# DLP.net
KiCad netlist of a schematic drawn in Altium Designer
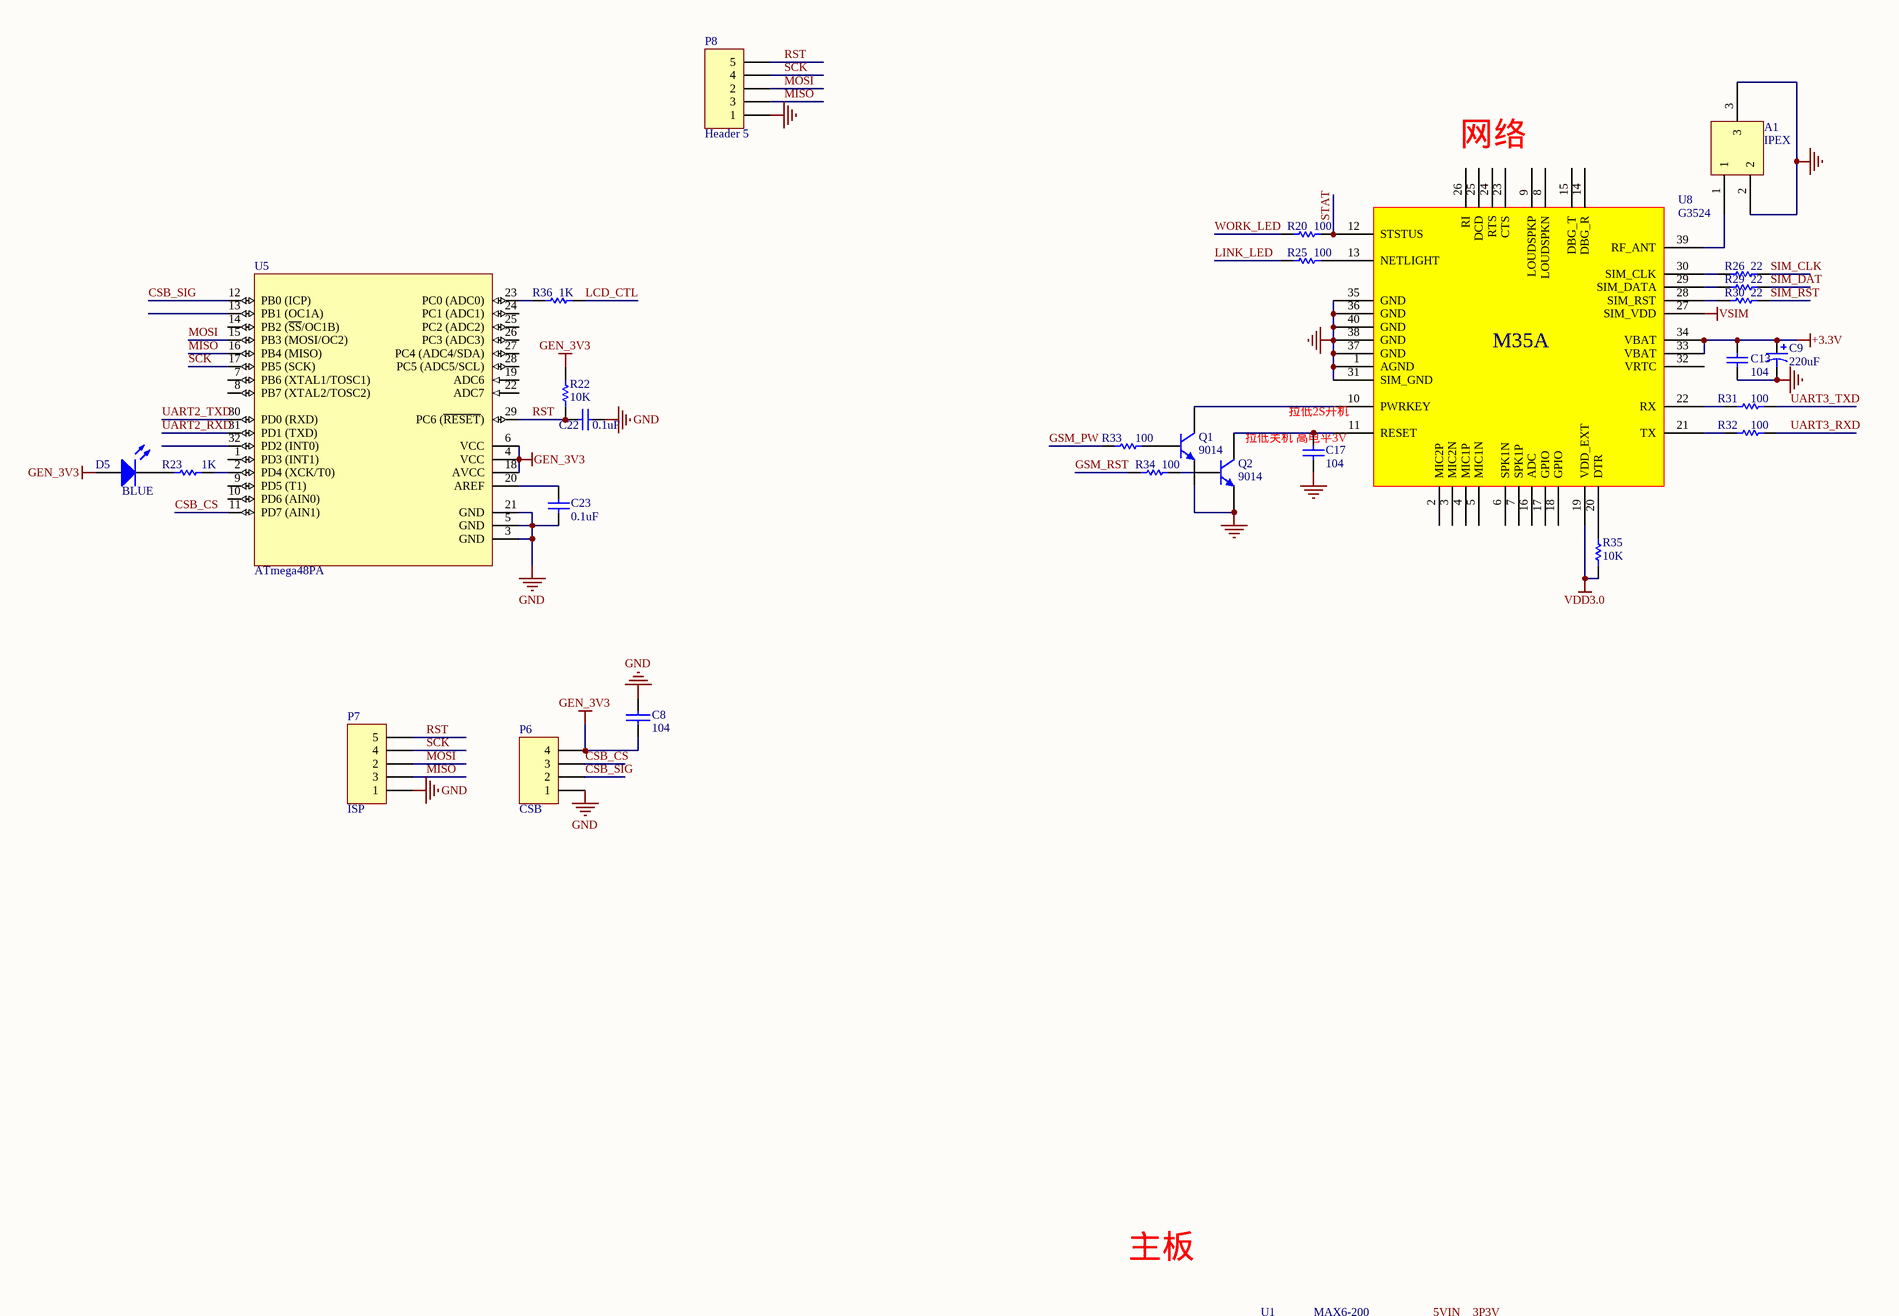
[diagram p0: DLP.SchDoc, top left]
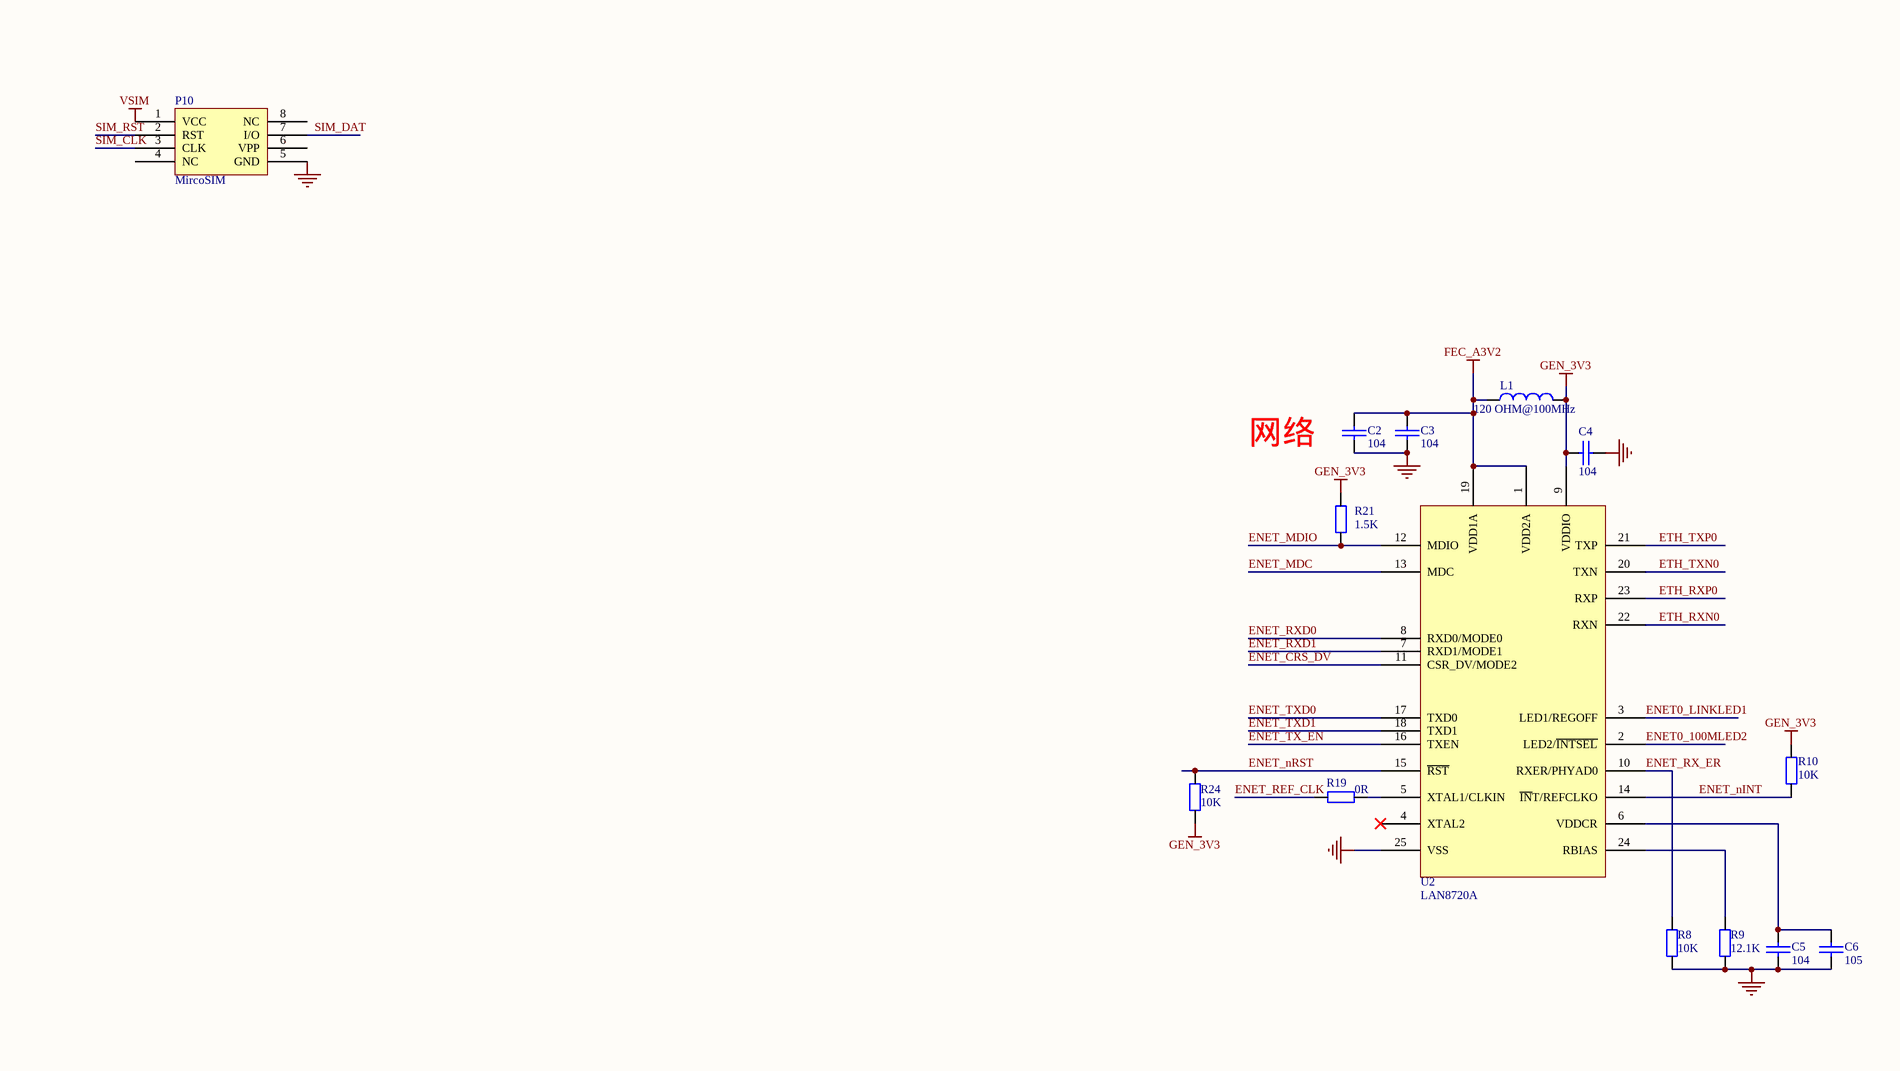
[diagram p1: DLP.SchDoc, top right]
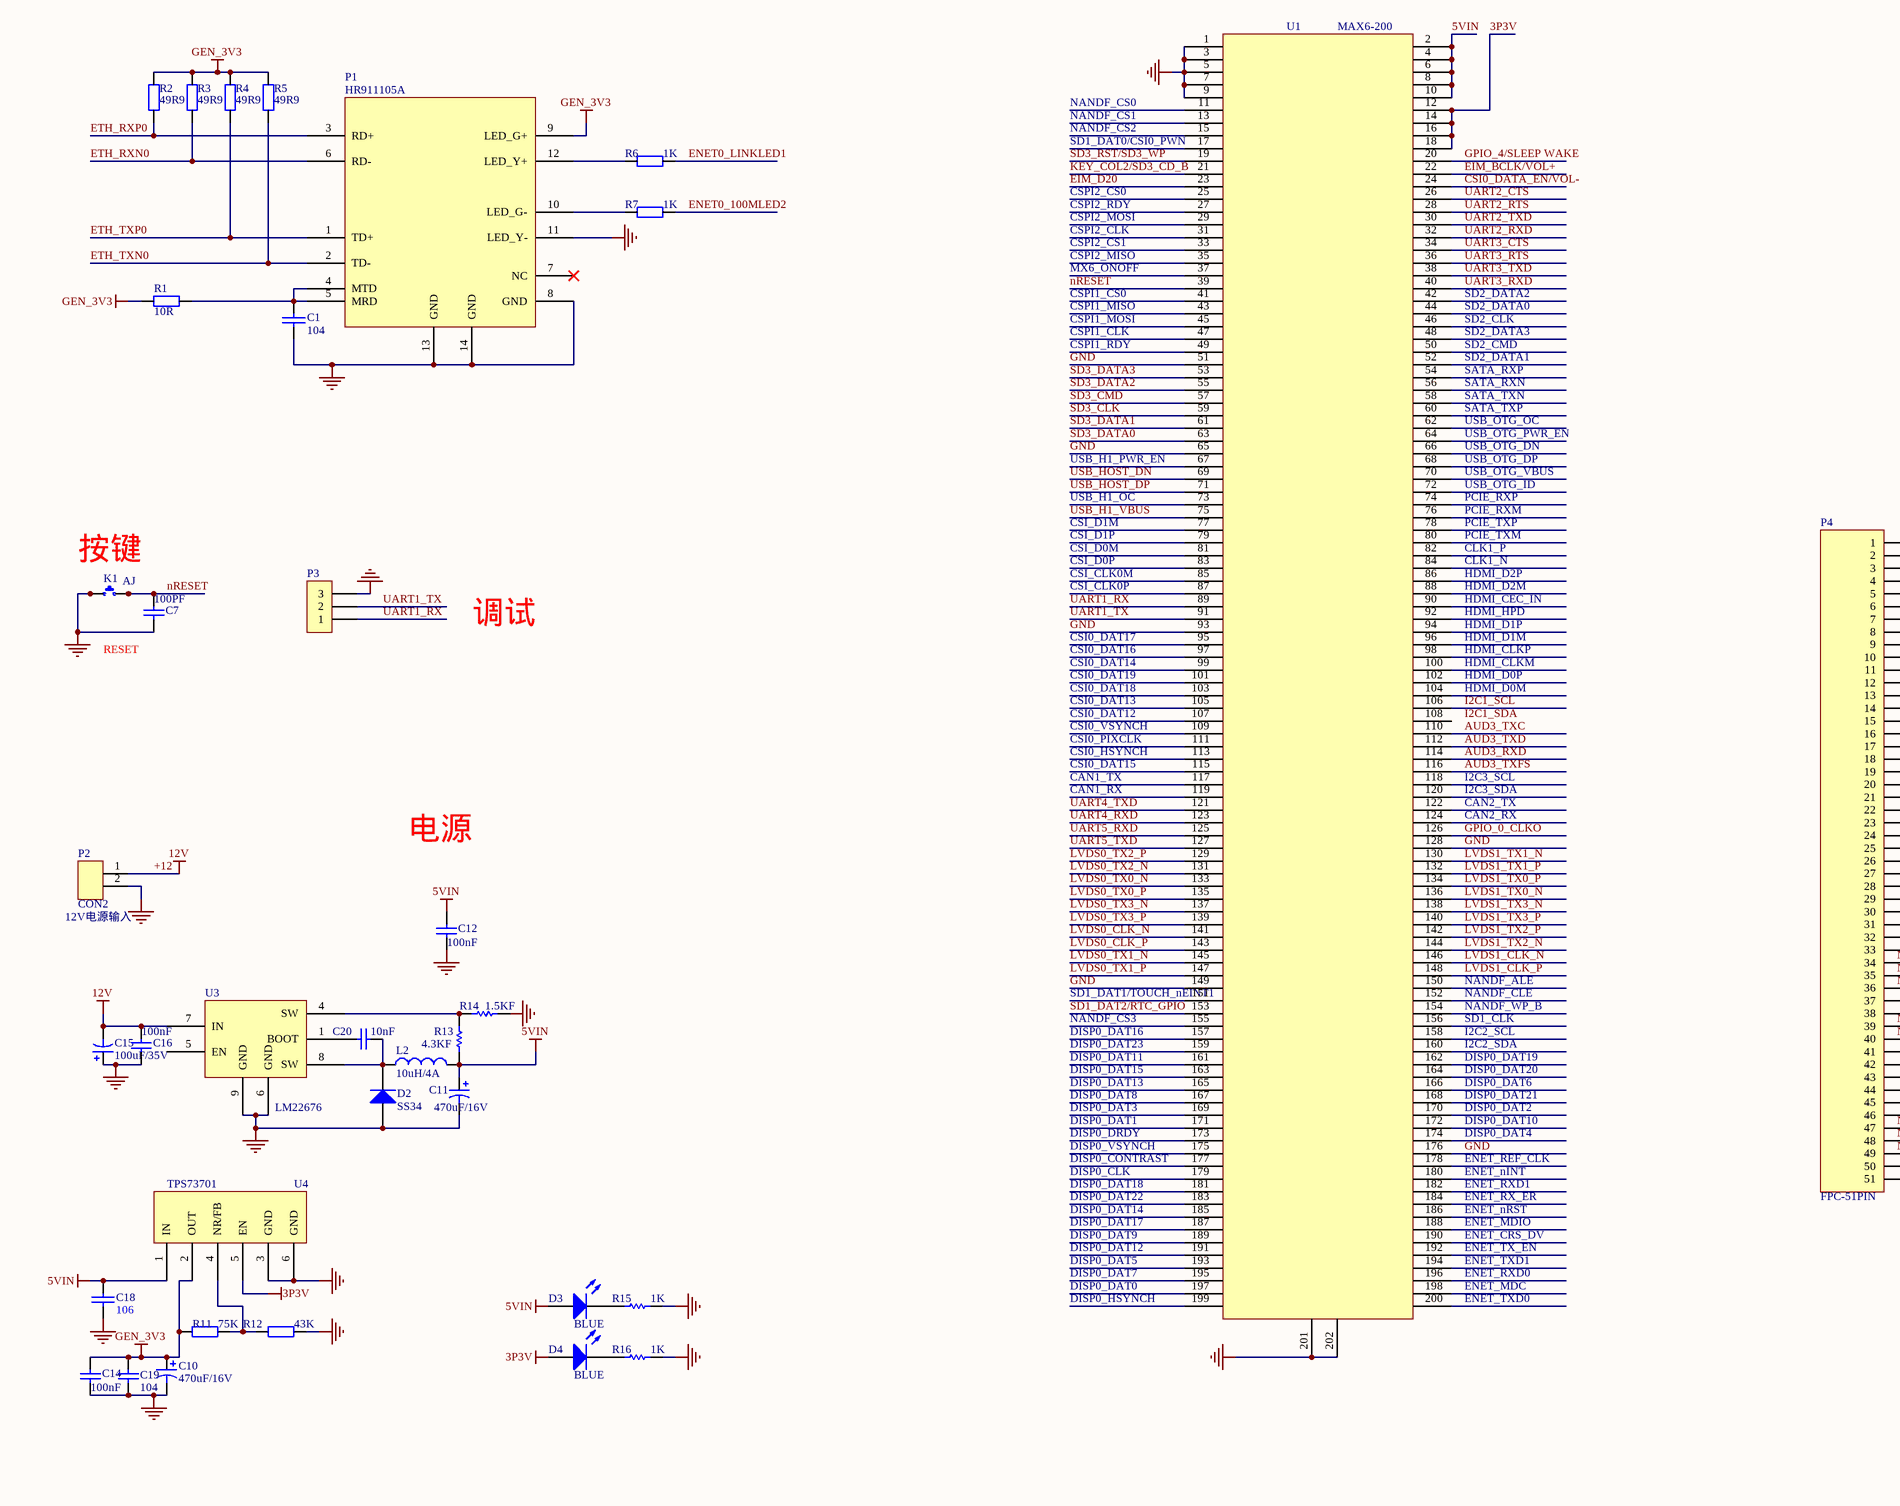
[diagram p2: DLP.SchDoc, bottom left]
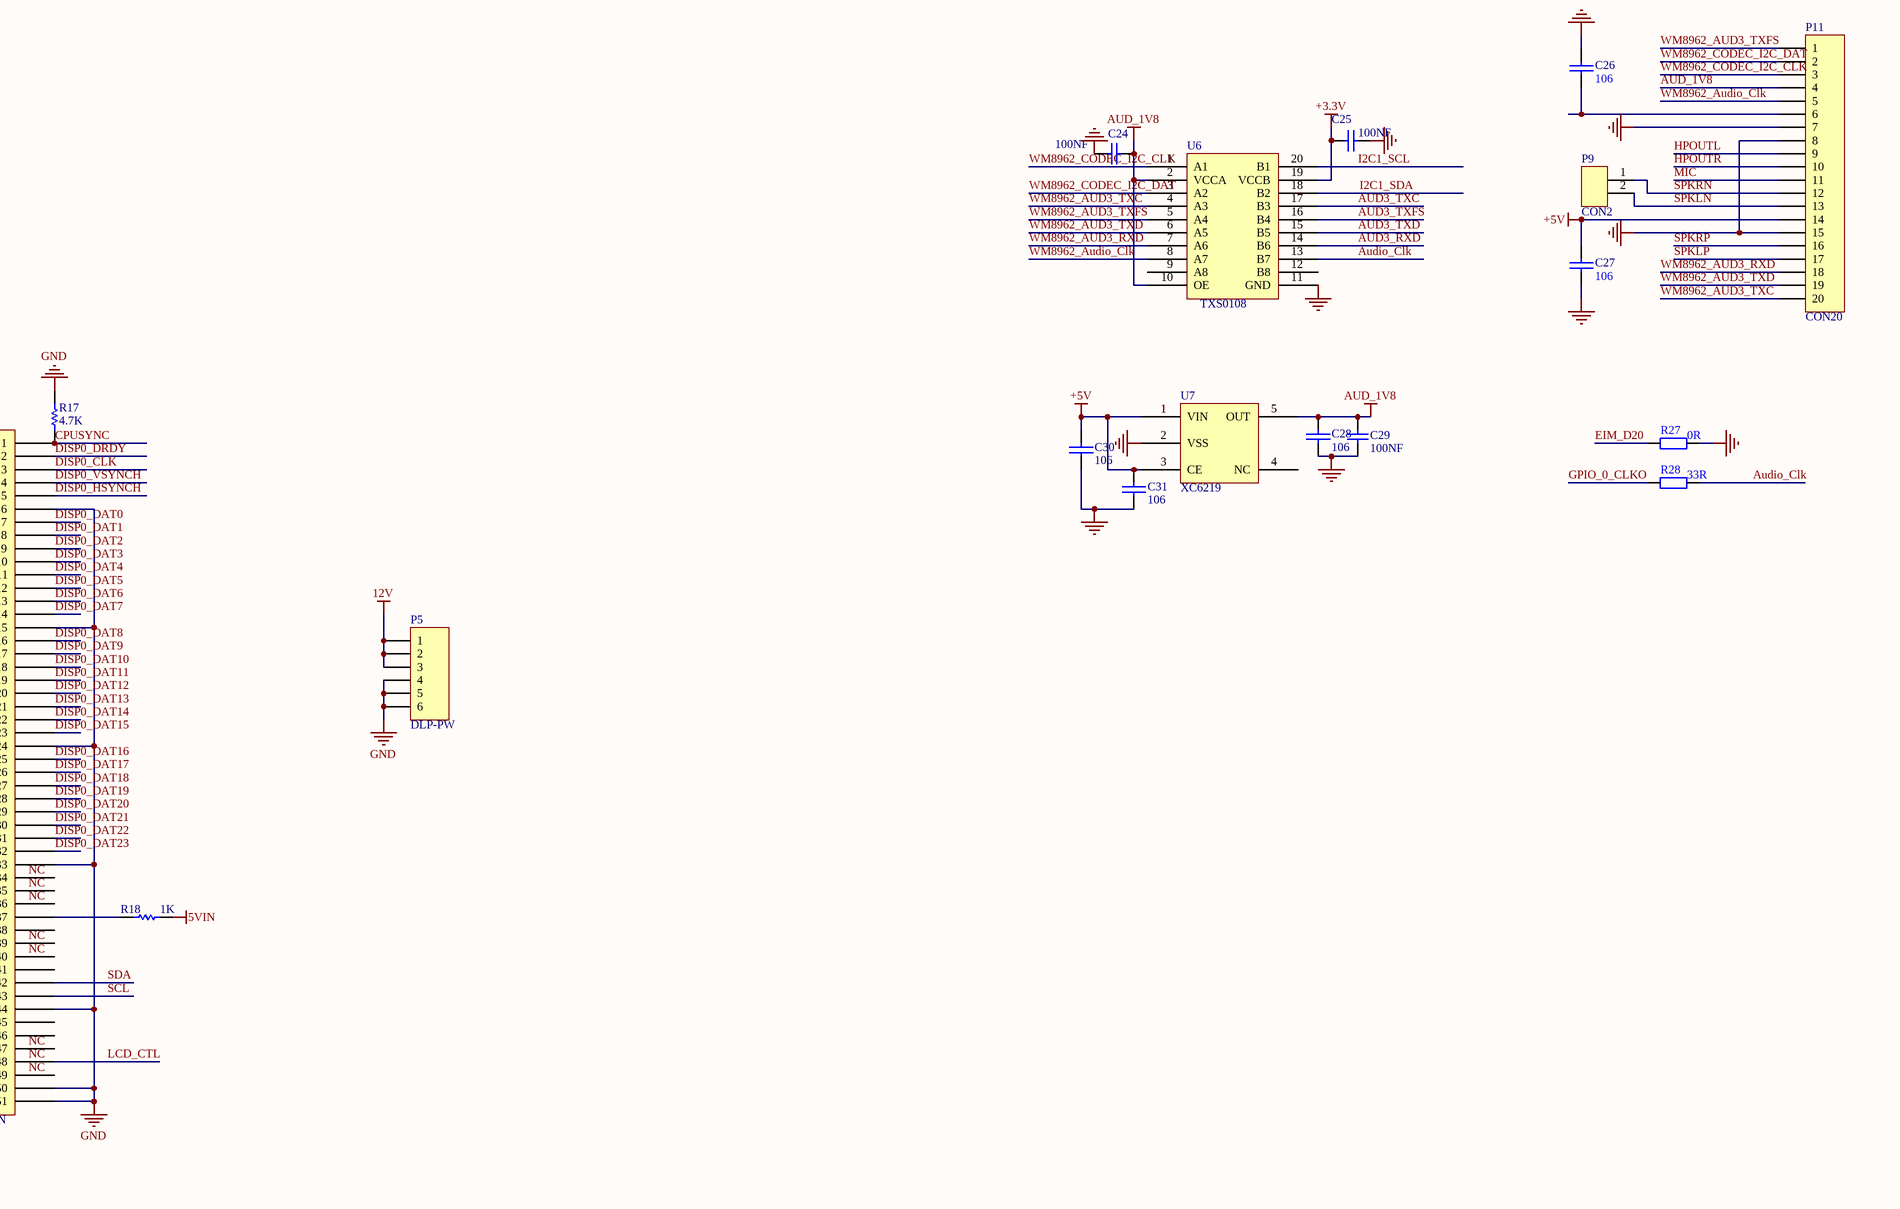
[diagram p3: DLP.SchDoc, bottom right]

(export (version "E")
  (design (tool "Eeschema 10.0.6"))
  (components
    (comp (ref "A1") (value "IPEX") (footprint "IPEX") (libsource (lib "*") (part "IPEX")))
    (comp (ref "C1") (value "104") (footprint "0603") (libsource (lib "*") (part "CAP")))
    (comp (ref "C2") (value "104") (footprint "0603") (libsource (lib "*") (part "CAP")))
    (comp (ref "C3") (value "104") (footprint "0603") (libsource (lib "*") (part "CAP")))
    (comp (ref "C4") (value "104") (footprint "0603") (libsource (lib "*") (part "CAP")))
    (comp (ref "C5") (value "104") (footprint "0603") (libsource (lib "*") (part "CAP")))
    (comp (ref "C6") (value "105") (footprint "0603") (libsource (lib "*") (part "CAP")))
    (comp (ref "C7")
      (value "100PF")
      (footprint "0603")
      (description "Capacitor")
      (libsource (lib "*") (part "Cap"))
    )
    (comp (ref "C8") (value "104") (footprint "0603") (libsource (lib "*") (part "CAP")))
    (comp (ref "C9")
      (value "220uF")
      (footprint "C7343")
      (description "Polarized Capacitor (Surface Mount)")
      (fields (field (name "Comment") "Cap Pol3") (field (name "PUBLISHER") "Altium Limited"))
      (libsource (lib "*") (part "Cap Pol3"))
    )
    (comp (ref "C10")
      (value "470uF/16V")
      (footprint "3216[1206]")
      (description "Polarized Capacitor (Radial)")
      (libsource (lib "*") (part "Cap Pol1"))
    )
    (comp (ref "C11")
      (value "470uF/16V")
      (footprint "C6.3*12")
      (description "Polarized Capacitor (Radial)")
      (libsource (lib "*") (part "Cap Pol1"))
    )
    (comp (ref "C12")
      (value "100nF")
      (footprint "0603")
      (description "Capacitor")
      (libsource (lib "*") (part "Cap"))
    )
    (comp (ref "C13")
      (value "104")
      (footprint "0603")
      (description "Capacitor")
      (fields (field (name "Comment") "Cap") (field (name "PUBLISHER") "Altium Limited"))
      (libsource (lib "*") (part "Cap"))
    )
    (comp (ref "C14")
      (value "100nF")
      (footprint "0603")
      (description "Capacitor")
      (libsource (lib "*") (part "Cap"))
    )
    (comp (ref "C15")
      (value "100uF/35V")
      (footprint "C8x4")
      (description "Polarized Capacitor (Radial)")
      (libsource (lib "*") (part "Cap Pol1"))
    )
    (comp (ref "C16")
      (value "100nF")
      (footprint "0603")
      (description "Capacitor")
      (libsource (lib "*") (part "Cap"))
    )
    (comp (ref "C17")
      (value "104")
      (footprint "0603")
      (description "Capacitor")
      (fields (field (name "Comment") "Cap") (field (name "PUBLISHER") "Altium Limited"))
      (libsource (lib "*") (part "Cap"))
    )
    (comp (ref "C18") (value "106") (footprint "C1206") (libsource (lib "") (part "CAP_1")))
    (comp (ref "C19")
      (value "104")
      (footprint "0603")
      (fields (field (name "PUBLISHER") "Altium Limited"))
      (libsource (lib "*") (part "Cap"))
    )
    (comp (ref "C20")
      (value "10nF")
      (footprint "0603")
      (description "Capacitor")
      (libsource (lib "*") (part "Cap"))
    )
    (comp (ref "C22")
      (value "0.1uF")
      (footprint "0603")
      (description "Capacitor")
      (fields (field (name "Comment") "Cap") (field (name "PUBLISHER") "Altium Limited"))
      (libsource (lib "Miscellaneous Devices") (part "Cap"))
    )
    (comp (ref "C23")
      (value "0.1uF")
      (footprint "0603")
      (description "Capacitor")
      (fields (field (name "Comment") "Cap") (field (name "PUBLISHER") "Altium Limited"))
      (libsource (lib "Miscellaneous Devices") (part "Cap"))
    )
    (comp (ref "C24")
      (value "100NF")
      (footprint "0603")
      (fields (field (name "PUBLISHER") "Altium Limited"))
      (libsource (lib "*") (part "Cap"))
    )
    (comp (ref "C25")
      (value "100NF")
      (footprint "0603")
      (fields (field (name "PUBLISHER") "Altium Limited"))
      (libsource (lib "*") (part "Cap"))
    )
    (comp (ref "C26") (value "106") (footprint "0603") (libsource (lib "") (part "CAP_1")))
    (comp (ref "C27") (value "106") (footprint "0603") (libsource (lib "") (part "CAP_1")))
    (comp (ref "C28") (value "106") (footprint "0603") (libsource (lib "") (part "CAP_2")))
    (comp (ref "C29")
      (value "100NF")
      (footprint "0603")
      (fields (field (name "PUBLISHER") "Altium Limited"))
      (libsource (lib "*") (part "Cap"))
    )
    (comp (ref "C30") (value "106") (footprint "0603") (libsource (lib "") (part "CAP_2")))
    (comp (ref "C31") (value "106") (footprint "0603") (libsource (lib "") (part "CAP_2")))
    (comp (ref "D2")
      (value "SS34")
      (footprint "SMA")
      (description "3 Amp Medium Power Silicon Rectifier Diode")
      (libsource (lib "*") (part "Diode 1N5408"))
    )
    (comp (ref "D3")
      (value "BLUE")
      (footprint "0603-LED")
      (description "Typical RED, GREEN, YELLOW, AMBER GaAs LED")
      (libsource (lib "*") (part "LED2"))
    )
    (comp (ref "D4")
      (value "BLUE")
      (footprint "0603-LED")
      (description "Typical RED, GREEN, YELLOW, AMBER GaAs LED")
      (libsource (lib "*") (part "LED2"))
    )
    (comp (ref "D5")
      (value "BLUE")
      (footprint "0603-LED")
      (description "Typical RED, GREEN, YELLOW, AMBER GaAs LED")
      (libsource (lib "*") (part "LED2"))
    )
    (comp (ref "K1") (value "AJ") (footprint "4*4*1.5") (libsource (lib "*") (part "KEY_1")))
    (comp (ref "L1")
      (value "120 OHM@100MHz")
      (footprint "0603")
      (description "Inductor")
      (libsource (lib "*") (part "Inductor"))
    )
    (comp (ref "L2")
      (value "10uH/4A")
      (footprint "8040")
      (description "Inductor")
      (libsource (lib "*") (part "Inductor"))
    )
    (comp (ref "P1") (value "HR911105A") (footprint "HR911105A") (libsource (lib "*") (part "HR911105A")))
    (comp (ref "P2") (value "CON2") (footprint "PH2.0-2P") (libsource (lib "*") (part "CON2")))
    (comp (ref "P3")
      (value "~")
      (footprint "HDR1X3")
      (description "Connector")
      (libsource (lib "*") (part "CON3"))
    )
    (comp (ref "P4")
      (value "FPC-51PIN")
      (footprint "FH26-51S-0.3SHW")
      (libsource (lib "TANK") (part "FPC-51PIN"))
    )
    (comp (ref "P5")
      (value "DLP-PW")
      (footprint "SH1.0-6P")
      (description "Header, 6-Pin")
      (fields (field (name "PUBLISHER") "Altium Limited"))
      (libsource (lib "Miscellaneous Connectors") (part "Header 6"))
    )
    (comp (ref "P6")
      (value "CSB")
      (footprint "HDR1X4")
      (description "Header, 4-Pin")
      (fields (field (name "PUBLISHER") "Altium Limited"))
      (libsource (lib "Miscellaneous Connectors") (part "Header 4"))
    )
    (comp (ref "P7")
      (value "ISP")
      (footprint "HDR1X5")
      (description "Header, 5-Pin")
      (fields (field (name "PUBLISHER") "Altium Limited"))
      (libsource (lib "Miscellaneous Connectors") (part "Header 5"))
    )
    (comp (ref "P8")
      (value "Header 5")
      (footprint "HDR1X5")
      (description "Header, 5-Pin")
      (fields (field (name "PUBLISHER") "Altium Limited"))
      (libsource (lib "*") (part "Header 5"))
    )
    (comp (ref "P9") (value "CON2") (footprint "PH2.0-2P") (libsource (lib "") (part "CON2_1")))
    (comp (ref "P10") (value "MircoSIM") (footprint "Micro SIM") (libsource (lib "*") (part "MircoSIM")))
    (comp (ref "P11") (value "CON20") (footprint "WM8962") (libsource (lib "*") (part "CON20")))
    (comp (ref "Q1")
      (value "9014")
      (footprint "SOT-23-NPN")
      (description "NPN General Purpose Amplifier")
      (fields (field (name "Comment") "NPN") (field (name "PUBLISHER") "Altium Limited"))
      (libsource (lib "*") (part "2N5551"))
    )
    (comp (ref "Q2")
      (value "9014")
      (footprint "SOT-23-NPN")
      (description "NPN General Purpose Amplifier")
      (fields (field (name "Comment") "NPN") (field (name "PUBLISHER") "Altium Limited"))
      (libsource (lib "*") (part "2N5551"))
    )
    (comp (ref "R1") (value "10R") (footprint "0603") (libsource (lib "*") (part "RES")))
    (comp (ref "R2") (value "49R9") (footprint "0603") (libsource (lib "*") (part "RES")))
    (comp (ref "R3") (value "49R9") (footprint "0603") (libsource (lib "*") (part "RES")))
    (comp (ref "R4") (value "49R9") (footprint "0603") (libsource (lib "*") (part "RES")))
    (comp (ref "R5") (value "49R9") (footprint "0603") (libsource (lib "*") (part "RES")))
    (comp (ref "R6") (value "1K") (footprint "0603") (libsource (lib "*") (part "RES")))
    (comp (ref "R7") (value "1K") (footprint "0603") (libsource (lib "*") (part "RES")))
    (comp (ref "R8") (value "10K") (footprint "0603") (libsource (lib "*") (part "RES")))
    (comp (ref "R9") (value "12.1K") (footprint "0603") (libsource (lib "*") (part "RES")))
    (comp (ref "R10") (value "10K") (footprint "0603") (libsource (lib "*") (part "RES")))
    (comp (ref "R11")
      (value "75K")
      (footprint "0603")
      (description "Resistor")
      (fields (field (name "PUBLISHER") "Altium Limited"))
      (libsource (lib "*") (part "Res2"))
    )
    (comp (ref "R12")
      (value "43K")
      (footprint "0603")
      (description "Resistor")
      (fields (field (name "PUBLISHER") "Altium Limited"))
      (libsource (lib "") (part "Res2_1"))
    )
    (comp (ref "R13")
      (value "4.3KF")
      (footprint "0603")
      (description "Resistor")
      (libsource (lib "*") (part "Res1"))
    )
    (comp (ref "R14")
      (value "1.5KF")
      (footprint "0603")
      (description "Resistor")
      (libsource (lib "*") (part "Res1"))
    )
    (comp (ref "R15")
      (value "1K")
      (footprint "0603")
      (description "Resistor")
      (libsource (lib "*") (part "Res1"))
    )
    (comp (ref "R16")
      (value "1K")
      (footprint "0603")
      (description "Resistor")
      (libsource (lib "*") (part "Res1"))
    )
    (comp (ref "R17")
      (value "4.7K")
      (footprint "0603")
      (description "Resistor")
      (fields (field (name "Comment") "Res1") (field (name "PUBLISHER") "Altium Limited"))
      (libsource (lib "Miscellaneous Devices") (part "Res1"))
    )
    (comp (ref "R18")
      (value "1K")
      (footprint "0603")
      (description "Resistor")
      (libsource (lib "*") (part "Res1"))
    )
    (comp (ref "R19") (value "0R") (footprint "0603") (libsource (lib "*") (part "RES")))
    (comp (ref "R20")
      (value "100")
      (footprint "0603")
      (description "Resistor")
      (fields (field (name "Comment") "Res1") (field (name "PUBLISHER") "Altium Limited"))
      (libsource (lib "*") (part "Res1"))
    )
    (comp (ref "R21") (value "1.5K") (footprint "0603") (libsource (lib "*") (part "RES")))
    (comp (ref "R22")
      (value "10K")
      (footprint "0603")
      (description "Resistor")
      (fields (field (name "Comment") "Res1") (field (name "PUBLISHER") "Altium Limited"))
      (libsource (lib "Miscellaneous Devices") (part "Res1"))
    )
    (comp (ref "R23")
      (value "1K")
      (footprint "0603")
      (description "Resistor")
      (libsource (lib "*") (part "Res1"))
    )
    (comp (ref "R24") (value "10K") (footprint "0603") (libsource (lib "*") (part "RES")))
    (comp (ref "R25")
      (value "100")
      (footprint "0603")
      (description "Resistor")
      (fields (field (name "Comment") "Res1") (field (name "PUBLISHER") "Altium Limited"))
      (libsource (lib "*") (part "Res1"))
    )
    (comp (ref "R26")
      (value "22")
      (footprint "0603")
      (description "Resistor")
      (fields (field (name "Comment") "Res1") (field (name "PUBLISHER") "Altium Limited"))
      (libsource (lib "*") (part "Res1"))
    )
    (comp (ref "R27") (value "0R") (footprint "0603") (libsource (lib "") (part "RES_1")))
    (comp (ref "R28") (value "33R") (footprint "0603") (libsource (lib "") (part "RES_1")))
    (comp (ref "R29")
      (value "22")
      (footprint "0603")
      (description "Resistor")
      (fields (field (name "Comment") "Res1") (field (name "PUBLISHER") "Altium Limited"))
      (libsource (lib "*") (part "Res1"))
    )
    (comp (ref "R30")
      (value "22")
      (footprint "0603")
      (description "Resistor")
      (fields (field (name "Comment") "Res1") (field (name "PUBLISHER") "Altium Limited"))
      (libsource (lib "*") (part "Res1"))
    )
    (comp (ref "R31")
      (value "100")
      (footprint "0603")
      (description "Resistor")
      (fields (field (name "Comment") "Res1") (field (name "PUBLISHER") "Altium Limited"))
      (libsource (lib "*") (part "Res1"))
    )
    (comp (ref "R32")
      (value "100")
      (footprint "0603")
      (description "Resistor")
      (fields (field (name "Comment") "Res1") (field (name "PUBLISHER") "Altium Limited"))
      (libsource (lib "*") (part "Res1"))
    )
    (comp (ref "R33")
      (value "100")
      (footprint "0603")
      (description "Resistor")
      (fields (field (name "Comment") "Res1") (field (name "PUBLISHER") "Altium Limited"))
      (libsource (lib "*") (part "Res1"))
    )
    (comp (ref "R34")
      (value "100")
      (footprint "0603")
      (description "Resistor")
      (fields (field (name "Comment") "Res1") (field (name "PUBLISHER") "Altium Limited"))
      (libsource (lib "*") (part "Res1"))
    )
    (comp (ref "R35")
      (value "10K")
      (footprint "0603")
      (description "Resistor")
      (fields (field (name "Comment") "Res1") (field (name "PUBLISHER") "Altium Limited"))
      (libsource (lib "*") (part "Res1"))
    )
    (comp (ref "R36")
      (value "1K")
      (footprint "0603")
      (description "Resistor")
      (libsource (lib "*") (part "Res1"))
    )
    (comp (ref "U1") (value "MAX6-200") (footprint "SO-DIMM 200") (libsource (lib "*") (part "MAX6-200")))
    (comp (ref "U2") (value "LAN8720A") (footprint "QFN24_4X4MM") (libsource (lib "*") (part "LAN8720A")))
    (comp (ref "U3") (value "LM22676") (footprint "SO-8HP") (libsource (lib "*") (part "LM22676")))
    (comp (ref "U4") (value "TPS73701") (footprint "SOT223-6") (libsource (lib "*") (part "TPS737")))
    (comp (ref "U5")
      (value "ATmega48PA")
      (footprint "32A_M")
      (description "8-Bit AVR Microcontroller with 8K Bytes of In-System Programmable Flash Memory")
      (fields (field (name "PUBLISHER") "Altium Limited"))
      (libsource (lib "Atmel Microcontroller 8-Bit AVR") (part "ATmega8-16AC"))
    )
    (comp (ref "U6") (value "TXS0108") (footprint "TSSOP-20") (libsource (lib "*") (part "TXS0108")))
    (comp (ref "U7") (value "XC6219") (footprint "SOT23-5N") (libsource (lib "*") (part "XC6219")))
    (comp (ref "U8") (value "G3524") (footprint "G3524") (libsource (lib "*") (part "G3524")))
  )
  (nets
    (net (code "1") (name "+3.3V") (class "Default")
      (node (ref "C13") (pin "2") (pinfunction "2_2") (pintype "passive"))
      (node (ref "C25") (pin "1") (pinfunction "1_1") (pintype "passive"))
      (node (ref "C9") (pin "1") (pinfunction "1_1") (pintype "passive"))
      (node (ref "U6") (pin "19") (pinfunction "VCCB_19") (pintype "passive"))
      (node (ref "U8") (pin "33") (pinfunction "VBAT_33") (pintype "passive"))
      (node (ref "U8") (pin "34") (pinfunction "VBAT_34") (pintype "passive"))
    )
    (net (code "2") (name "+5V") (class "Default")
      (node (ref "C27") (pin "2") (pintype "passive"))
      (node (ref "C30") (pin "1") (pintype "passive"))
      (node (ref "C31") (pin "1") (pintype "passive"))
      (node (ref "P11") (pin "14") (pinfunction "14_14") (pintype "passive"))
      (node (ref "U7") (pin "1") (pinfunction "VIN_1") (pintype "passive"))
      (node (ref "U7") (pin "3") (pinfunction "CE_3") (pintype "passive"))
    )
    (net (code "3") (name "/AUD3_RXD") (class "Default")
      (node (ref "U1") (pin "114") (pintype "passive"))
      (node (ref "U6") (pin "14") (pinfunction "B6_14") (pintype "passive"))
    )
    (net (code "4") (name "/AUD3_TXC") (class "Default")
      (node (ref "U1") (pin "110") (pintype "passive"))
      (node (ref "U6") (pin "17") (pinfunction "B3_17") (pintype "passive"))
    )
    (net (code "5") (name "/AUD3_TXD") (class "Default")
      (node (ref "U1") (pin "112") (pintype "passive"))
      (node (ref "U6") (pin "15") (pinfunction "B5_15") (pintype "passive"))
    )
    (net (code "6") (name "/AUD3_TXFS") (class "Default")
      (node (ref "U1") (pin "116") (pintype "passive"))
      (node (ref "U6") (pin "16") (pinfunction "B4_16") (pintype "passive"))
    )
    (net (code "7") (name "/Audio_Clk") (class "Default")
      (node (ref "R28") (pin "1") (pinfunction "1_1") (pintype "passive"))
      (node (ref "U6") (pin "13") (pinfunction "B7_13") (pintype "passive"))
    )
    (net (code "8") (name "/CAN1_RX") (class "Default") (node (ref "U1") (pin "119") (pintype "passive")))
    (net (code "9") (name "/CAN1_TX") (class "Default") (node (ref "U1") (pin "117") (pintype "passive")))
    (net (code "10") (name "/CAN2_RX") (class "Default") (node (ref "U1") (pin "124") (pintype "passive")))
    (net (code "11") (name "/CAN2_TX") (class "Default") (node (ref "U1") (pin "122") (pintype "passive")))
    (net (code "12") (name "/CLK1_N") (class "Default") (node (ref "U1") (pin "84") (pintype "passive")))
    (net (code "13") (name "/CLK1_P") (class "Default") (node (ref "U1") (pin "82") (pintype "passive")))
    (net (code "14") (name "/CPUSYNC") (class "Default")
      (node (ref "P4") (pin "1") (pinfunction "1_1") (pintype "passive"))
      (node (ref "R17") (pin "2") (pinfunction "2_2") (pintype "passive"))
    )
    (net (code "15") (name "/CSB_CS") (class "Default")
      (node (ref "P6") (pin "3") (pinfunction "3_3") (pintype "passive"))
      (node (ref "U5") (pin "11") (pinfunction "PD7_(AIN1)_11") (pintype "bidirectional"))
    )
    (net (code "16") (name "/CSB_SIG") (class "Default")
      (node (ref "P6") (pin "2") (pinfunction "2_2") (pintype "passive"))
      (node (ref "U5") (pin "12") (pinfunction "PB0_(ICP)_12") (pintype "bidirectional"))
    )
    (net (code "17") (name "/CSI0_DAT12") (class "Default") (node (ref "U1") (pin "107") (pintype "passive")))
    (net (code "18") (name "/CSI0_DAT13") (class "Default") (node (ref "U1") (pin "105") (pintype "passive")))
    (net (code "19") (name "/CSI0_DAT14") (class "Default") (node (ref "U1") (pin "99") (pintype "passive")))
    (net (code "20") (name "/CSI0_DAT15") (class "Default") (node (ref "U1") (pin "115") (pintype "passive")))
    (net (code "21") (name "/CSI0_DAT16") (class "Default") (node (ref "U1") (pin "97") (pintype "passive")))
    (net (code "22") (name "/CSI0_DAT17") (class "Default") (node (ref "U1") (pin "95") (pintype "passive")))
    (net (code "23") (name "/CSI0_DAT18") (class "Default") (node (ref "U1") (pin "103") (pintype "passive")))
    (net (code "24") (name "/CSI0_DAT19") (class "Default") (node (ref "U1") (pin "101") (pintype "passive")))
    (net (code "25") (name "/CSI0_DATA_EN{slash}VOL-") (class "Default")
      (node (ref "U1") (pin "24") (pintype "passive"))
    )
    (net (code "26") (name "/CSI0_HSYNCH") (class "Default")
      (node (ref "U1") (pin "113") (pintype "passive"))
    )
    (net (code "27") (name "/CSI0_PIXCLK") (class "Default")
      (node (ref "U1") (pin "111") (pintype "passive"))
    )
    (net (code "28") (name "/CSI0_VSYNCH") (class "Default")
      (node (ref "U1") (pin "109") (pintype "passive"))
    )
    (net (code "29") (name "/CSI_CLK0M") (class "Default") (node (ref "U1") (pin "85") (pintype "passive")))
    (net (code "30") (name "/CSI_CLK0P") (class "Default") (node (ref "U1") (pin "87") (pintype "passive")))
    (net (code "31") (name "/CSI_D0M") (class "Default") (node (ref "U1") (pin "81") (pintype "passive")))
    (net (code "32") (name "/CSI_D0P") (class "Default") (node (ref "U1") (pin "83") (pintype "passive")))
    (net (code "33") (name "/CSI_D1M") (class "Default") (node (ref "U1") (pin "77") (pintype "passive")))
    (net (code "34") (name "/CSI_D1P") (class "Default") (node (ref "U1") (pin "79") (pintype "passive")))
    (net (code "35") (name "/CSPI1_CLK") (class "Default") (node (ref "U1") (pin "47") (pintype "passive")))
    (net (code "36") (name "/CSPI1_CS0") (class "Default") (node (ref "U1") (pin "41") (pintype "passive")))
    (net (code "37") (name "/CSPI1_MISO") (class "Default") (node (ref "U1") (pin "43") (pintype "passive")))
    (net (code "38") (name "/CSPI1_MOSI") (class "Default") (node (ref "U1") (pin "45") (pintype "passive")))
    (net (code "39") (name "/CSPI1_RDY") (class "Default") (node (ref "U1") (pin "49") (pintype "passive")))
    (net (code "40") (name "/CSPI2_CLK") (class "Default") (node (ref "U1") (pin "31") (pintype "passive")))
    (net (code "41") (name "/CSPI2_CS0") (class "Default") (node (ref "U1") (pin "25") (pintype "passive")))
    (net (code "42") (name "/CSPI2_CS1") (class "Default") (node (ref "U1") (pin "33") (pintype "passive")))
    (net (code "43") (name "/CSPI2_MISO") (class "Default") (node (ref "U1") (pin "35") (pintype "passive")))
    (net (code "44") (name "/CSPI2_MOSI") (class "Default") (node (ref "U1") (pin "29") (pintype "passive")))
    (net (code "45") (name "/CSPI2_RDY") (class "Default") (node (ref "U1") (pin "27") (pintype "passive")))
    (net (code "46") (name "/DISP0_CLK") (class "Default")
      (node (ref "P4") (pin "3") (pinfunction "3_3") (pintype "passive"))
      (node (ref "U1") (pin "179") (pintype "passive"))
    )
    (net (code "47") (name "/DISP0_CONTRAST") (class "Default")
      (node (ref "U1") (pin "177") (pintype "passive"))
    )
    (net (code "48") (name "/DISP0_DAT0") (class "Default")
      (node (ref "P4") (pin "7") (pinfunction "7_7") (pintype "passive"))
      (node (ref "U1") (pin "197") (pintype "passive"))
    )
    (net (code "49") (name "/DISP0_DAT1") (class "Default")
      (node (ref "P4") (pin "8") (pinfunction "8_8") (pintype "passive"))
      (node (ref "U1") (pin "171") (pintype "passive"))
    )
    (net (code "50") (name "/DISP0_DAT2") (class "Default")
      (node (ref "P4") (pin "9") (pinfunction "9_9") (pintype "passive"))
      (node (ref "U1") (pin "170") (pintype "passive"))
    )
    (net (code "51") (name "/DISP0_DAT3") (class "Default")
      (node (ref "P4") (pin "10") (pinfunction "10_10") (pintype "passive"))
      (node (ref "U1") (pin "169") (pintype "passive"))
    )
    (net (code "52") (name "/DISP0_DAT4") (class "Default")
      (node (ref "P4") (pin "11") (pinfunction "11_11") (pintype "passive"))
      (node (ref "U1") (pin "174") (pintype "passive"))
    )
    (net (code "53") (name "/DISP0_DAT5") (class "Default")
      (node (ref "P4") (pin "12") (pinfunction "12_12") (pintype "passive"))
      (node (ref "U1") (pin "193") (pintype "passive"))
    )
    (net (code "54") (name "/DISP0_DAT6") (class "Default")
      (node (ref "P4") (pin "13") (pinfunction "13_13") (pintype "passive"))
      (node (ref "U1") (pin "166") (pintype "passive"))
    )
    (net (code "55") (name "/DISP0_DAT7") (class "Default")
      (node (ref "P4") (pin "14") (pinfunction "14_14") (pintype "passive"))
      (node (ref "U1") (pin "195") (pintype "passive"))
    )
    (net (code "56") (name "/DISP0_DAT8") (class "Default")
      (node (ref "P4") (pin "16") (pinfunction "16_16") (pintype "passive"))
      (node (ref "U1") (pin "167") (pintype "passive"))
    )
    (net (code "57") (name "/DISP0_DAT9") (class "Default")
      (node (ref "P4") (pin "17") (pinfunction "17_17") (pintype "passive"))
      (node (ref "U1") (pin "189") (pintype "passive"))
    )
    (net (code "58") (name "/DISP0_DAT10") (class "Default")
      (node (ref "P4") (pin "18") (pinfunction "18_18") (pintype "passive"))
      (node (ref "U1") (pin "172") (pintype "passive"))
    )
    (net (code "59") (name "/DISP0_DAT11") (class "Default")
      (node (ref "P4") (pin "19") (pinfunction "19_19") (pintype "passive"))
      (node (ref "U1") (pin "161") (pintype "passive"))
    )
    (net (code "60") (name "/DISP0_DAT12") (class "Default")
      (node (ref "P4") (pin "20") (pinfunction "20_20") (pintype "passive"))
      (node (ref "U1") (pin "191") (pintype "passive"))
    )
    (net (code "61") (name "/DISP0_DAT13") (class "Default")
      (node (ref "P4") (pin "21") (pinfunction "21_21") (pintype "passive"))
      (node (ref "U1") (pin "165") (pintype "passive"))
    )
    (net (code "62") (name "/DISP0_DAT14") (class "Default")
      (node (ref "P4") (pin "22") (pinfunction "22_22") (pintype "passive"))
      (node (ref "U1") (pin "185") (pintype "passive"))
    )
    (net (code "63") (name "/DISP0_DAT15") (class "Default")
      (node (ref "P4") (pin "23") (pinfunction "23_23") (pintype "passive"))
      (node (ref "U1") (pin "163") (pintype "passive"))
    )
    (net (code "64") (name "/DISP0_DAT16") (class "Default")
      (node (ref "P4") (pin "25") (pinfunction "25_25") (pintype "passive"))
      (node (ref "U1") (pin "157") (pintype "passive"))
    )
    (net (code "65") (name "/DISP0_DAT17") (class "Default")
      (node (ref "P4") (pin "26") (pinfunction "26_26") (pintype "passive"))
      (node (ref "U1") (pin "187") (pintype "passive"))
    )
    (net (code "66") (name "/DISP0_DAT18") (class "Default")
      (node (ref "P4") (pin "27") (pinfunction "27_27") (pintype "passive"))
      (node (ref "U1") (pin "181") (pintype "passive"))
    )
    (net (code "67") (name "/DISP0_DAT19") (class "Default")
      (node (ref "P4") (pin "28") (pinfunction "28_28") (pintype "passive"))
      (node (ref "U1") (pin "162") (pintype "passive"))
    )
    (net (code "68") (name "/DISP0_DAT20") (class "Default")
      (node (ref "P4") (pin "29") (pinfunction "29_29") (pintype "passive"))
      (node (ref "U1") (pin "164") (pintype "passive"))
    )
    (net (code "69") (name "/DISP0_DAT21") (class "Default")
      (node (ref "P4") (pin "30") (pinfunction "30_30") (pintype "passive"))
      (node (ref "U1") (pin "168") (pintype "passive"))
    )
    (net (code "70") (name "/DISP0_DAT22") (class "Default")
      (node (ref "P4") (pin "31") (pinfunction "31_31") (pintype "passive"))
      (node (ref "U1") (pin "183") (pintype "passive"))
    )
    (net (code "71") (name "/DISP0_DAT23") (class "Default")
      (node (ref "P4") (pin "32") (pinfunction "32_32") (pintype "passive"))
      (node (ref "U1") (pin "159") (pintype "passive"))
    )
    (net (code "72") (name "/DISP0_DRDY") (class "Default")
      (node (ref "P4") (pin "2") (pinfunction "2_2") (pintype "passive"))
      (node (ref "U1") (pin "173") (pintype "passive"))
    )
    (net (code "73") (name "/DISP0_HSYNCH") (class "Default")
      (node (ref "P4") (pin "5") (pinfunction "5_5") (pintype "passive"))
      (node (ref "U1") (pin "199") (pintype "passive"))
    )
    (net (code "74") (name "/DISP0_VSYNCH") (class "Default")
      (node (ref "P4") (pin "4") (pinfunction "4_4") (pintype "passive"))
      (node (ref "U1") (pin "175") (pintype "passive"))
    )
    (net (code "75") (name "/EIM_BCLK{slash}VOL+") (class "Default")
      (node (ref "U1") (pin "22") (pintype "passive"))
    )
    (net (code "76") (name "/EIM_D20") (class "Default")
      (node (ref "R27") (pin "2") (pinfunction "2_2") (pintype "passive"))
      (node (ref "U1") (pin "23") (pintype "passive"))
    )
    (net (code "77") (name "/ENET0_100MLED2") (class "Default")
      (node (ref "R7") (pin "2") (pinfunction "2_2") (pintype "passive"))
      (node (ref "U2") (pin "2") (pinfunction "LED2/~{INTSEL}_2") (pintype "passive"))
    )
    (net (code "78") (name "/ENET0_LINKLED1") (class "Default")
      (node (ref "R6") (pin "2") (pinfunction "2_2") (pintype "passive"))
      (node (ref "U2") (pin "3") (pinfunction "LED1/REGOFF_3") (pintype "passive"))
    )
    (net (code "79") (name "/ENET_CRS_DV") (class "Default")
      (node (ref "U1") (pin "190") (pintype "passive"))
      (node (ref "U2") (pin "11") (pinfunction "CSR_DV/MODE2_11") (pintype "passive"))
    )
    (net (code "80") (name "/ENET_MDC") (class "Default")
      (node (ref "U1") (pin "198") (pintype "passive"))
      (node (ref "U2") (pin "13") (pinfunction "MDC_13") (pintype "passive"))
    )
    (net (code "81") (name "/ENET_MDIO") (class "Default")
      (node (ref "R21") (pin "1") (pinfunction "1_1") (pintype "passive"))
      (node (ref "U1") (pin "188") (pintype "passive"))
      (node (ref "U2") (pin "12") (pinfunction "MDIO_12") (pintype "passive"))
    )
    (net (code "82") (name "/ENET_REF_CLK") (class "Default")
      (node (ref "R19") (pin "2") (pinfunction "2_2") (pintype "passive"))
      (node (ref "U1") (pin "178") (pintype "passive"))
    )
    (net (code "83") (name "/ENET_RXD0") (class "Default")
      (node (ref "U1") (pin "196") (pintype "passive"))
      (node (ref "U2") (pin "8") (pinfunction "RXD0/MODE0_8") (pintype "passive"))
    )
    (net (code "84") (name "/ENET_RXD1") (class "Default")
      (node (ref "U1") (pin "182") (pintype "passive"))
      (node (ref "U2") (pin "7") (pinfunction "RXD1/MODE1_7") (pintype "passive"))
    )
    (net (code "85") (name "/ENET_RX_ER") (class "Default")
      (node (ref "R8") (pin "2") (pinfunction "2_2") (pintype "passive"))
      (node (ref "U1") (pin "184") (pintype "passive"))
      (node (ref "U2") (pin "10") (pinfunction "RXER/PHYAD0_10") (pintype "passive"))
    )
    (net (code "86") (name "/ENET_TXD0") (class "Default")
      (node (ref "U1") (pin "200") (pintype "passive"))
      (node (ref "U2") (pin "17") (pinfunction "TXD0_17") (pintype "passive"))
    )
    (net (code "87") (name "/ENET_TXD1") (class "Default")
      (node (ref "U1") (pin "194") (pintype "passive"))
      (node (ref "U2") (pin "18") (pinfunction "TXD1_18") (pintype "passive"))
    )
    (net (code "88") (name "/ENET_TX_EN") (class "Default")
      (node (ref "U1") (pin "192") (pintype "passive"))
      (node (ref "U2") (pin "16") (pinfunction "TXEN_16") (pintype "passive"))
    )
    (net (code "89") (name "/ENET_nINT") (class "Default")
      (node (ref "R10") (pin "1") (pinfunction "1_1") (pintype "passive"))
      (node (ref "U1") (pin "180") (pintype "passive"))
      (node (ref "U2") (pin "14") (pinfunction "~{IN}T/REFCLKO_14") (pintype "passive"))
    )
    (net (code "90") (name "/ENET_nRST") (class "Default")
      (node (ref "R24") (pin "2") (pinfunction "2_2") (pintype "passive"))
      (node (ref "U1") (pin "186") (pintype "passive"))
      (node (ref "U2") (pin "15") (pinfunction "~{RST}_15") (pintype "passive"))
    )
    (net (code "91") (name "/ETH_RXN0") (class "Default")
      (node (ref "P1") (pin "6") (pinfunction "RD-_6") (pintype "passive"))
      (node (ref "R3") (pin "1") (pinfunction "1_1") (pintype "passive"))
      (node (ref "U2") (pin "22") (pinfunction "RXN_22") (pintype "passive"))
    )
    (net (code "92") (name "/ETH_RXP0") (class "Default")
      (node (ref "P1") (pin "3") (pinfunction "RD+_3") (pintype "passive"))
      (node (ref "R2") (pin "1") (pinfunction "1_1") (pintype "passive"))
      (node (ref "U2") (pin "23") (pinfunction "RXP_23") (pintype "passive"))
    )
    (net (code "93") (name "/ETH_TXN0") (class "Default")
      (node (ref "P1") (pin "2") (pinfunction "TD-_2") (pintype "passive"))
      (node (ref "R5") (pin "1") (pinfunction "1_1") (pintype "passive"))
      (node (ref "U2") (pin "20") (pinfunction "TXN_20") (pintype "passive"))
    )
    (net (code "94") (name "/ETH_TXP0") (class "Default")
      (node (ref "P1") (pin "1") (pinfunction "TD+_1") (pintype "passive"))
      (node (ref "R4") (pin "1") (pinfunction "1_1") (pintype "passive"))
      (node (ref "U2") (pin "21") (pinfunction "TXP_21") (pintype "passive"))
    )
    (net (code "95") (name "/GPIO_0_CLKO") (class "Default")
      (node (ref "R28") (pin "2") (pinfunction "2_2") (pintype "passive"))
      (node (ref "U1") (pin "126") (pintype "passive"))
    )
    (net (code "96") (name "/GPIO_4{slash}SLEEP WAKE") (class "Default")
      (node (ref "U1") (pin "20") (pintype "passive"))
    )
    (net (code "97") (name "/GSM_PW") (class "Default")
      (node (ref "R33") (pin "2") (pinfunction "2_2") (pintype "passive"))
    )
    (net (code "98") (name "/GSM_RST") (class "Default")
      (node (ref "R34") (pin "2") (pinfunction "2_2") (pintype "passive"))
    )
    (net (code "99") (name "/HDMI_CEC_IN") (class "Default") (node (ref "U1") (pin "90") (pintype "passive")))
    (net (code "100") (name "/HDMI_CLKM") (class "Default") (node (ref "U1") (pin "100") (pintype "passive")))
    (net (code "101") (name "/HDMI_CLKP") (class "Default") (node (ref "U1") (pin "98") (pintype "passive")))
    (net (code "102") (name "/HDMI_D0M") (class "Default") (node (ref "U1") (pin "104") (pintype "passive")))
    (net (code "103") (name "/HDMI_D0P") (class "Default") (node (ref "U1") (pin "102") (pintype "passive")))
    (net (code "104") (name "/HDMI_D1M") (class "Default") (node (ref "U1") (pin "96") (pintype "passive")))
    (net (code "105") (name "/HDMI_D1P") (class "Default") (node (ref "U1") (pin "94") (pintype "passive")))
    (net (code "106") (name "/HDMI_D2M") (class "Default") (node (ref "U1") (pin "88") (pintype "passive")))
    (net (code "107") (name "/HDMI_D2P") (class "Default") (node (ref "U1") (pin "86") (pintype "passive")))
    (net (code "108") (name "/HDMI_HPD") (class "Default") (node (ref "U1") (pin "92") (pintype "passive")))
    (net (code "109") (name "/HPOUTL") (class "Default")
      (node (ref "P11") (pin "9") (pinfunction "9_9") (pintype "passive"))
    )
    (net (code "110") (name "/HPOUTR") (class "Default")
      (node (ref "P11") (pin "10") (pinfunction "10_10") (pintype "passive"))
    )
    (net (code "111") (name "/I2C1_SCL") (class "Default")
      (node (ref "U1") (pin "106") (pintype "passive"))
      (node (ref "U6") (pin "20") (pinfunction "B1_20") (pintype "passive"))
    )
    (net (code "112") (name "/I2C1_SDA") (class "Default")
      (node (ref "U6") (pin "18") (pinfunction "B2_18") (pintype "passive"))
    )
    (net (code "113") (name "/I2C2_SCL") (class "Default") (node (ref "U1") (pin "158") (pintype "passive")))
    (net (code "114") (name "/I2C2_SDA") (class "Default") (node (ref "U1") (pin "160") (pintype "passive")))
    (net (code "115") (name "/I2C3_SCL") (class "Default") (node (ref "U1") (pin "118") (pintype "passive")))
    (net (code "116") (name "/I2C3_SDA") (class "Default") (node (ref "U1") (pin "120") (pintype "passive")))
    (net (code "117") (name "/KEY_COL2{slash}SD3_CD_B") (class "Default")
      (node (ref "U1") (pin "21") (pintype "passive"))
    )
    (net (code "118") (name "/LCD_CTL") (class "Default")
      (node (ref "P4") (pin "48") (pinfunction "48_48") (pintype "passive"))
      (node (ref "R36") (pin "1") (pinfunction "1_1") (pintype "passive"))
    )
    (net (code "119") (name "/LINK_LED") (class "Default")
      (node (ref "R25") (pin "2") (pinfunction "2_2") (pintype "passive"))
    )
    (net (code "120") (name "/LVDS0_CLK_N") (class "Default")
      (node (ref "U1") (pin "141") (pintype "passive"))
    )
    (net (code "121") (name "/LVDS0_CLK_P") (class "Default")
      (node (ref "U1") (pin "143") (pintype "passive"))
    )
    (net (code "122") (name "/LVDS0_TX0_N") (class "Default")
      (node (ref "U1") (pin "133") (pintype "passive"))
    )
    (net (code "123") (name "/LVDS0_TX0_P") (class "Default")
      (node (ref "U1") (pin "135") (pintype "passive"))
    )
    (net (code "124") (name "/LVDS0_TX1_N") (class "Default")
      (node (ref "U1") (pin "145") (pintype "passive"))
    )
    (net (code "125") (name "/LVDS0_TX1_P") (class "Default")
      (node (ref "U1") (pin "147") (pintype "passive"))
    )
    (net (code "126") (name "/LVDS0_TX2_N") (class "Default")
      (node (ref "U1") (pin "131") (pintype "passive"))
    )
    (net (code "127") (name "/LVDS0_TX2_P") (class "Default")
      (node (ref "U1") (pin "129") (pintype "passive"))
    )
    (net (code "128") (name "/LVDS0_TX3_N") (class "Default")
      (node (ref "U1") (pin "137") (pintype "passive"))
    )
    (net (code "129") (name "/LVDS0_TX3_P") (class "Default")
      (node (ref "U1") (pin "139") (pintype "passive"))
    )
    (net (code "130") (name "/LVDS1_CLK_N") (class "Default")
      (node (ref "U1") (pin "146") (pintype "passive"))
    )
    (net (code "131") (name "/LVDS1_CLK_P") (class "Default")
      (node (ref "U1") (pin "148") (pintype "passive"))
    )
    (net (code "132") (name "/LVDS1_TX0_N") (class "Default")
      (node (ref "U1") (pin "136") (pintype "passive"))
    )
    (net (code "133") (name "/LVDS1_TX0_P") (class "Default")
      (node (ref "U1") (pin "134") (pintype "passive"))
    )
    (net (code "134") (name "/LVDS1_TX1_N") (class "Default")
      (node (ref "U1") (pin "130") (pintype "passive"))
    )
    (net (code "135") (name "/LVDS1_TX1_P") (class "Default")
      (node (ref "U1") (pin "132") (pintype "passive"))
    )
    (net (code "136") (name "/LVDS1_TX2_N") (class "Default")
      (node (ref "U1") (pin "144") (pintype "passive"))
    )
    (net (code "137") (name "/LVDS1_TX2_P") (class "Default")
      (node (ref "U1") (pin "142") (pintype "passive"))
    )
    (net (code "138") (name "/LVDS1_TX3_N") (class "Default")
      (node (ref "U1") (pin "138") (pintype "passive"))
    )
    (net (code "139") (name "/LVDS1_TX3_P") (class "Default")
      (node (ref "U1") (pin "140") (pintype "passive"))
    )
    (net (code "140") (name "/MIC") (class "Default")
      (node (ref "P11") (pin "11") (pinfunction "11_11") (pintype "passive"))
    )
    (net (code "141") (name "/MISO") (class "Default")
      (node (ref "P7") (pin "3") (pinfunction "3_3") (pintype "passive"))
      (node (ref "P8") (pin "3") (pinfunction "3_3") (pintype "passive"))
      (node (ref "U5") (pin "16") (pinfunction "PB4_(MISO)_16") (pintype "bidirectional"))
    )
    (net (code "142") (name "/MOSI") (class "Default")
      (node (ref "P7") (pin "2") (pinfunction "2_2") (pintype "passive"))
      (node (ref "P8") (pin "2") (pinfunction "2_2") (pintype "passive"))
      (node (ref "U5") (pin "15") (pinfunction "PB3_(MOSI/OC2)_15") (pintype "bidirectional"))
    )
    (net (code "143") (name "/MX6_ONOFF") (class "Default") (node (ref "U1") (pin "37") (pintype "passive")))
    (net (code "144") (name "/NANDF_ALE") (class "Default") (node (ref "U1") (pin "150") (pintype "passive")))
    (net (code "145") (name "/NANDF_CLE") (class "Default") (node (ref "U1") (pin "152") (pintype "passive")))
    (net (code "146") (name "/NANDF_CS0") (class "Default") (node (ref "U1") (pin "11") (pintype "passive")))
    (net (code "147") (name "/NANDF_CS1") (class "Default") (node (ref "U1") (pin "13") (pintype "passive")))
    (net (code "148") (name "/NANDF_CS2") (class "Default") (node (ref "U1") (pin "15") (pintype "passive")))
    (net (code "149") (name "/NANDF_CS3") (class "Default") (node (ref "U1") (pin "155") (pintype "passive")))
    (net (code "150") (name "/NANDF_WP_B") (class "Default")
      (node (ref "U1") (pin "154") (pintype "passive"))
    )
    (net (code "152") (name "/PCIE_RXM") (class "Default") (node (ref "U1") (pin "76") (pintype "passive")))
    (net (code "153") (name "/PCIE_RXP") (class "Default") (node (ref "U1") (pin "74") (pintype "passive")))
    (net (code "154") (name "/PCIE_TXM") (class "Default") (node (ref "U1") (pin "80") (pintype "passive")))
    (net (code "155") (name "/PCIE_TXP") (class "Default") (node (ref "U1") (pin "78") (pintype "passive")))
    (net (code "156") (name "/RST") (class "Default")
      (node (ref "C22") (pin "1") (pinfunction "1_1") (pintype "passive"))
      (node (ref "P7") (pin "5") (pinfunction "5_5") (pintype "passive"))
      (node (ref "P8") (pin "5") (pinfunction "5_5") (pintype "passive"))
      (node (ref "R22") (pin "1") (pinfunction "1_1") (pintype "passive"))
      (node (ref "U5") (pin "29") (pinfunction "PC6_(~{RESET})_29") (pintype "bidirectional"))
    )
    (net (code "157") (name "/SATA_RXN") (class "Default") (node (ref "U1") (pin "56") (pintype "passive")))
    (net (code "158") (name "/SATA_RXP") (class "Default") (node (ref "U1") (pin "54") (pintype "passive")))
    (net (code "159") (name "/SATA_TXN") (class "Default") (node (ref "U1") (pin "58") (pintype "passive")))
    (net (code "160") (name "/SATA_TXP") (class "Default") (node (ref "U1") (pin "60") (pintype "passive")))
    (net (code "161") (name "/SCK") (class "Default")
      (node (ref "P7") (pin "4") (pinfunction "4_4") (pintype "passive"))
      (node (ref "P8") (pin "4") (pinfunction "4_4") (pintype "passive"))
      (node (ref "U5") (pin "17") (pinfunction "PB5_(SCK)_17") (pintype "bidirectional"))
    )
    (net (code "162") (name "/SCL") (class "Default")
      (node (ref "P4") (pin "43") (pinfunction "43_43") (pintype "passive"))
    )
    (net (code "163") (name "/SD1_CLK") (class "Default") (node (ref "U1") (pin "156") (pintype "passive")))
    (net (code "164") (name "/SD1_DAT0{slash}CSI0_PWN") (class "Default")
      (node (ref "U1") (pin "17") (pintype "passive"))
    )
    (net (code "165") (name "/SD1_DAT1{slash}TOUCH_nEINT1") (class "Default")
      (node (ref "U1") (pin "151") (pintype "passive"))
    )
    (net (code "166") (name "/SD1_DAT2{slash}RTC_GPIO") (class "Default")
      (node (ref "U1") (pin "153") (pintype "passive"))
    )
    (net (code "167") (name "/SD2_CLK") (class "Default") (node (ref "U1") (pin "46") (pintype "passive")))
    (net (code "168") (name "/SD2_CMD") (class "Default") (node (ref "U1") (pin "50") (pintype "passive")))
    (net (code "169") (name "/SD2_DATA0") (class "Default") (node (ref "U1") (pin "44") (pintype "passive")))
    (net (code "170") (name "/SD2_DATA1") (class "Default") (node (ref "U1") (pin "52") (pintype "passive")))
    (net (code "171") (name "/SD2_DATA2") (class "Default") (node (ref "U1") (pin "42") (pintype "passive")))
    (net (code "172") (name "/SD2_DATA3") (class "Default") (node (ref "U1") (pin "48") (pintype "passive")))
    (net (code "173") (name "/SD3_CLK") (class "Default") (node (ref "U1") (pin "59") (pintype "passive")))
    (net (code "174") (name "/SD3_CMD") (class "Default") (node (ref "U1") (pin "57") (pintype "passive")))
    (net (code "175") (name "/SD3_DATA0") (class "Default") (node (ref "U1") (pin "63") (pintype "passive")))
    (net (code "176") (name "/SD3_DATA1") (class "Default") (node (ref "U1") (pin "61") (pintype "passive")))
    (net (code "177") (name "/SD3_DATA2") (class "Default") (node (ref "U1") (pin "55") (pintype "passive")))
    (net (code "178") (name "/SD3_DATA3") (class "Default") (node (ref "U1") (pin "53") (pintype "passive")))
    (net (code "179") (name "/SD3_RST{slash}SD3_WP") (class "Default")
      (node (ref "U1") (pin "19") (pintype "passive"))
    )
    (net (code "180") (name "/SDA") (class "Default")
      (node (ref "P4") (pin "42") (pinfunction "42_42") (pintype "passive"))
    )
    (net (code "181") (name "/SIM_CLK") (class "Default")
      (node (ref "P10") (pin "3") (pinfunction "CLK_3") (pintype "passive"))
      (node (ref "R26") (pin "1") (pinfunction "1_1") (pintype "passive"))
    )
    (net (code "182") (name "/SIM_DAT") (class "Default")
      (node (ref "P10") (pin "7") (pinfunction "I/O_7") (pintype "passive"))
      (node (ref "R29") (pin "1") (pinfunction "1_1") (pintype "passive"))
    )
    (net (code "183") (name "/SIM_RST") (class "Default")
      (node (ref "P10") (pin "2") (pinfunction "RST_2") (pintype "passive"))
      (node (ref "R30") (pin "1") (pinfunction "1_1") (pintype "passive"))
    )
    (net (code "184") (name "/SPKLN") (class "Default")
      (node (ref "P11") (pin "13") (pinfunction "13_13") (pintype "passive"))
      (node (ref "P9") (pin "2") (pinfunction "2_2") (pintype "passive"))
    )
    (net (code "185") (name "/SPKLP") (class "Default")
      (node (ref "P11") (pin "17") (pinfunction "17_17") (pintype "passive"))
    )
    (net (code "186") (name "/SPKRN") (class "Default")
      (node (ref "P11") (pin "12") (pinfunction "12_12") (pintype "passive"))
      (node (ref "P9") (pin "1") (pinfunction "1_1") (pintype "passive"))
    )
    (net (code "187") (name "/SPKRP") (class "Default")
      (node (ref "P11") (pin "16") (pinfunction "16_16") (pintype "passive"))
    )
    (net (code "188") (name "/STAT") (class "Default")
      (node (ref "R20") (pin "1") (pinfunction "1_1") (pintype "passive"))
      (node (ref "U8") (pin "12") (pinfunction "STSTUS_12") (pintype "passive"))
    )
    (net (code "189") (name "/UART1_RX") (class "Default")
      (node (ref "P3") (pin "1") (pinfunction "1_1") (pintype "passive"))
      (node (ref "U1") (pin "89") (pintype "passive"))
    )
    (net (code "190") (name "/UART1_TX") (class "Default")
      (node (ref "P3") (pin "2") (pinfunction "2_2") (pintype "passive"))
      (node (ref "U1") (pin "91") (pintype "passive"))
    )
    (net (code "191") (name "/UART2_CTS") (class "Default") (node (ref "U1") (pin "26") (pintype "passive")))
    (net (code "192") (name "/UART2_RTS") (class "Default") (node (ref "U1") (pin "28") (pintype "passive")))
    (net (code "193") (name "/UART2_RXD") (class "Default")
      (node (ref "U1") (pin "32") (pintype "passive"))
      (node (ref "U5") (pin "31") (pinfunction "PD1_(TXD)_31") (pintype "bidirectional"))
    )
    (net (code "194") (name "/UART2_TXD") (class "Default")
      (node (ref "U1") (pin "30") (pintype "passive"))
      (node (ref "U5") (pin "30") (pinfunction "PD0_(RXD)_30") (pintype "bidirectional"))
    )
    (net (code "195") (name "/UART3_CTS") (class "Default") (node (ref "U1") (pin "34") (pintype "passive")))
    (net (code "196") (name "/UART3_RTS") (class "Default") (node (ref "U1") (pin "36") (pintype "passive")))
    (net (code "197") (name "/UART3_RXD") (class "Default")
      (node (ref "R32") (pin "2") (pinfunction "2_2") (pintype "passive"))
      (node (ref "U1") (pin "40") (pintype "passive"))
    )
    (net (code "198") (name "/UART3_TXD") (class "Default")
      (node (ref "R31") (pin "2") (pinfunction "2_2") (pintype "passive"))
      (node (ref "U1") (pin "38") (pintype "passive"))
    )
    (net (code "199") (name "/UART4_RXD") (class "Default") (node (ref "U1") (pin "123") (pintype "passive")))
    (net (code "200") (name "/UART4_TXD") (class "Default") (node (ref "U1") (pin "121") (pintype "passive")))
    (net (code "201") (name "/UART5_RXD") (class "Default") (node (ref "U1") (pin "125") (pintype "passive")))
    (net (code "202") (name "/UART5_TXD") (class "Default") (node (ref "U1") (pin "127") (pintype "passive")))
    (net (code "203") (name "/USB_H1_OC") (class "Default") (node (ref "U1") (pin "73") (pintype "passive")))
    (net (code "204") (name "/USB_H1_PWR_EN") (class "Default")
      (node (ref "U1") (pin "67") (pintype "passive"))
    )
    (net (code "205") (name "/USB_H1_VBUS") (class "Default")
      (node (ref "U1") (pin "75") (pintype "passive"))
    )
    (net (code "206") (name "/USB_HOST_DN") (class "Default")
      (node (ref "U1") (pin "69") (pintype "passive"))
    )
    (net (code "207") (name "/USB_HOST_DP") (class "Default")
      (node (ref "U1") (pin "71") (pintype "passive"))
    )
    (net (code "208") (name "/USB_OTG_DN") (class "Default") (node (ref "U1") (pin "66") (pintype "passive")))
    (net (code "209") (name "/USB_OTG_DP") (class "Default") (node (ref "U1") (pin "68") (pintype "passive")))
    (net (code "210") (name "/USB_OTG_ID") (class "Default") (node (ref "U1") (pin "72") (pintype "passive")))
    (net (code "211") (name "/USB_OTG_OC") (class "Default") (node (ref "U1") (pin "62") (pintype "passive")))
    (net (code "212") (name "/USB_OTG_PWR_EN") (class "Default")
      (node (ref "U1") (pin "64") (pintype "passive"))
    )
    (net (code "213") (name "/USB_OTG_VBUS") (class "Default")
      (node (ref "U1") (pin "70") (pintype "passive"))
    )
    (net (code "214") (name "/WM8962_AUD3_RXD") (class "Default")
      (node (ref "P11") (pin "18") (pinfunction "18_18") (pintype "passive"))
      (node (ref "U6") (pin "7") (pinfunction "A6_7") (pintype "passive"))
    )
    (net (code "215") (name "/WM8962_AUD3_TXC") (class "Default")
      (node (ref "P11") (pin "20") (pinfunction "20_20") (pintype "passive"))
      (node (ref "U6") (pin "4") (pinfunction "A3_4") (pintype "passive"))
    )
    (net (code "216") (name "/WM8962_AUD3_TXD") (class "Default")
      (node (ref "P11") (pin "19") (pinfunction "19_19") (pintype "passive"))
      (node (ref "U6") (pin "6") (pinfunction "A5_6") (pintype "passive"))
    )
    (net (code "217") (name "/WM8962_AUD3_TXFS") (class "Default")
      (node (ref "P11") (pin "1") (pinfunction "1_1") (pintype "passive"))
      (node (ref "U6") (pin "5") (pinfunction "A4_5") (pintype "passive"))
    )
    (net (code "218") (name "/WM8962_Audio_Clk") (class "Default")
      (node (ref "P11") (pin "5") (pinfunction "5_5") (pintype "passive"))
      (node (ref "U6") (pin "8") (pinfunction "A7_8") (pintype "passive"))
    )
    (net (code "219") (name "/WM8962_CODEC_I2C_CLK") (class "Default")
      (node (ref "P11") (pin "3") (pinfunction "3_3") (pintype "passive"))
      (node (ref "U6") (pin "1") (pinfunction "A1_1") (pintype "passive"))
    )
    (net (code "220") (name "/WM8962_CODEC_I2C_DAT") (class "Default")
      (node (ref "P11") (pin "2") (pinfunction "2_2") (pintype "passive"))
      (node (ref "U6") (pin "3") (pinfunction "A2_3") (pintype "passive"))
    )
    (net (code "221") (name "/WORK_LED") (class "Default")
      (node (ref "R20") (pin "2") (pinfunction "2_2") (pintype "passive"))
    )
    (net (code "222") (name "/nRESET") (class "Default")
      (node (ref "C7") (pin "2") (pinfunction "2_2") (pintype "passive"))
      (node (ref "K1") (pin "3") (pintype "passive"))
      (node (ref "K1") (pin "4") (pintype "passive"))
      (node (ref "U1") (pin "39") (pintype "passive"))
    )
    (net (code "223") (name "3P3V") (class "Default")
      (node (ref "D4") (pin "1") (pinfunction "A_1") (pintype "passive"))
      (node (ref "U1") (pin "12") (pintype "passive"))
      (node (ref "U1") (pin "14") (pintype "passive"))
      (node (ref "U1") (pin "16") (pintype "passive"))
      (node (ref "U1") (pin "18") (pintype "passive"))
      (node (ref "U4") (pin "5") (pinfunction "EN_5") (pintype "passive"))
    )
    (net (code "224") (name "5VIN") (class "Default")
      (node (ref "C11") (pin "1") (pinfunction "1_1") (pintype "passive"))
      (node (ref "C12") (pin "2") (pinfunction "2_2") (pintype "passive"))
      (node (ref "C18") (pin "1") (pintype "passive"))
      (node (ref "D3") (pin "1") (pinfunction "A_1") (pintype "passive"))
      (node (ref "L2") (pin "2") (pinfunction "2_2") (pintype "passive"))
      (node (ref "R13") (pin "2") (pinfunction "2_2") (pintype "passive"))
      (node (ref "R18") (pin "1") (pinfunction "1_1") (pintype "passive"))
      (node (ref "U1") (pin "10") (pintype "passive"))
      (node (ref "U1") (pin "2") (pintype "passive"))
      (node (ref "U1") (pin "4") (pintype "passive"))
      (node (ref "U1") (pin "6") (pintype "passive"))
      (node (ref "U1") (pin "8") (pintype "passive"))
      (node (ref "U4") (pin "1") (pinfunction "IN_1") (pintype "passive"))
    )
    (net (code "225") (name "12V") (class "Default")
      (node (ref "C15") (pin "2") (pinfunction "2_2") (pintype "passive"))
      (node (ref "C16") (pin "2") (pinfunction "2_2") (pintype "passive"))
      (node (ref "P2") (pin "1") (pinfunction "1_1") (pintype "passive"))
      (node (ref "P5") (pin "1") (pinfunction "1_1") (pintype "passive"))
      (node (ref "P5") (pin "2") (pinfunction "2_2") (pintype "passive"))
      (node (ref "P5") (pin "3") (pinfunction "3_3") (pintype "passive"))
      (node (ref "U3") (pin "7") (pinfunction "IN_7") (pintype "passive"))
    )
    (net (code "226") (name "AUD_1V8") (class "Default")
      (node (ref "C24") (pin "2") (pinfunction "2_2") (pintype "passive"))
      (node (ref "C28") (pin "1") (pintype "passive"))
      (node (ref "C29") (pin "1") (pinfunction "1_1") (pintype "passive"))
      (node (ref "P11") (pin "4") (pinfunction "4_4") (pintype "passive"))
      (node (ref "U6") (pin "10") (pinfunction "OE_10") (pintype "passive"))
      (node (ref "U6") (pin "2") (pinfunction "VCCA_2") (pintype "passive"))
      (node (ref "U7") (pin "5") (pinfunction "OUT_5") (pintype "passive"))
    )
    (net (code "227") (name "FEC_A3V2") (class "Default")
      (node (ref "C2") (pin "1") (pintype "passive"))
      (node (ref "C3") (pin "1") (pintype "passive"))
      (node (ref "L1") (pin "1") (pinfunction "1_1") (pintype "passive"))
      (node (ref "U2") (pin "1") (pinfunction "VDD2A_1") (pintype "passive"))
      (node (ref "U2") (pin "19") (pinfunction "VDD1A_19") (pintype "passive"))
    )
    (net (code "228") (name "GEN_3V3") (class "Default")
      (node (ref "C10") (pin "1") (pinfunction "1_1") (pintype "passive"))
      (node (ref "C14") (pin "2") (pinfunction "2_2") (pintype "passive"))
      (node (ref "C19") (pin "2") (pinfunction "2_2") (pintype "passive"))
      (node (ref "C4") (pin "2") (pintype "passive"))
      (node (ref "C8") (pin "2") (pintype "passive"))
      (node (ref "D5") (pin "1") (pinfunction "A_1") (pintype "passive"))
      (node (ref "L1") (pin "2") (pinfunction "2_2") (pintype "passive"))
      (node (ref "P1") (pin "9") (pinfunction "LED_G+_9") (pintype "passive"))
      (node (ref "P6") (pin "4") (pinfunction "4_4") (pintype "passive"))
      (node (ref "R1") (pin "2") (pinfunction "2_2") (pintype "passive"))
      (node (ref "R10") (pin "2") (pinfunction "2_2") (pintype "passive"))
      (node (ref "R11") (pin "2") (pinfunction "2_2") (pintype "passive"))
      (node (ref "R2") (pin "2") (pinfunction "2_2") (pintype "passive"))
      (node (ref "R21") (pin "2") (pinfunction "2_2") (pintype "passive"))
      (node (ref "R22") (pin "2") (pinfunction "2_2") (pintype "passive"))
      (node (ref "R24") (pin "1") (pinfunction "1_1") (pintype "passive"))
      (node (ref "R3") (pin "2") (pinfunction "2_2") (pintype "passive"))
      (node (ref "R4") (pin "2") (pinfunction "2_2") (pintype "passive"))
      (node (ref "R5") (pin "2") (pinfunction "2_2") (pintype "passive"))
      (node (ref "U2") (pin "9") (pinfunction "VDDIO_9") (pintype "passive"))
      (node (ref "U4") (pin "2") (pinfunction "OUT_2") (pintype "passive"))
      (node (ref "U5") (pin "18") (pinfunction "AVCC_18") (pintype "power_in"))
      (node (ref "U5") (pin "4") (pinfunction "VCC_4") (pintype "power_in"))
      (node (ref "U5") (pin "6") (pinfunction "VCC_6") (pintype "power_in"))
    )
    (net (code "229") (name "GND") (class "Default")
      (node (ref "A1") (pin "2") (pinfunction "2_2") (pintype "passive"))
      (node (ref "A1") (pin "3") (pinfunction "3_3") (pintype "passive"))
      (node (ref "C1") (pin "2") (pintype "passive"))
      (node (ref "C10") (pin "2") (pinfunction "2_2") (pintype "passive"))
      (node (ref "C11") (pin "2") (pinfunction "2_2") (pintype "passive"))
      (node (ref "C12") (pin "1") (pinfunction "1_1") (pintype "passive"))
      (node (ref "C13") (pin "1") (pinfunction "1_1") (pintype "passive"))
      (node (ref "C14") (pin "1") (pinfunction "1_1") (pintype "passive"))
      (node (ref "C15") (pin "1") (pinfunction "1_1") (pintype "passive"))
      (node (ref "C16") (pin "1") (pinfunction "1_1") (pintype "passive"))
      (node (ref "C17") (pin "2") (pinfunction "2_2") (pintype "passive"))
      (node (ref "C18") (pin "2") (pintype "passive"))
      (node (ref "C19") (pin "1") (pinfunction "1_1") (pintype "passive"))
      (node (ref "C2") (pin "2") (pintype "passive"))
      (node (ref "C22") (pin "2") (pinfunction "2_2") (pintype "passive"))
      (node (ref "C23") (pin "2") (pinfunction "2_2") (pintype "passive"))
      (node (ref "C24") (pin "1") (pinfunction "1_1") (pintype "passive"))
      (node (ref "C25") (pin "2") (pinfunction "2_2") (pintype "passive"))
      (node (ref "C26") (pin "1") (pintype "passive"))
      (node (ref "C27") (pin "1") (pintype "passive"))
      (node (ref "C28") (pin "2") (pintype "passive"))
      (node (ref "C29") (pin "2") (pinfunction "2_2") (pintype "passive"))
      (node (ref "C3") (pin "2") (pintype "passive"))
      (node (ref "C30") (pin "2") (pintype "passive"))
      (node (ref "C31") (pin "2") (pintype "passive"))
      (node (ref "C4") (pin "1") (pintype "passive"))
      (node (ref "C5") (pin "2") (pintype "passive"))
      (node (ref "C6") (pin "2") (pintype "passive"))
      (node (ref "C7") (pin "1") (pinfunction "1_1") (pintype "passive"))
      (node (ref "C8") (pin "1") (pintype "passive"))
      (node (ref "C9") (pin "2") (pinfunction "2_2") (pintype "passive"))
      (node (ref "D2") (pin "1") (pinfunction "A_1") (pintype "passive"))
      (node (ref "K1") (pin "1") (pintype "passive"))
      (node (ref "K1") (pin "2") (pintype "passive"))
      (node (ref "P1") (pin "11") (pinfunction "LED_Y-_11") (pintype "passive"))
      (node (ref "P1") (pin "13") (pinfunction "GND_13") (pintype "passive"))
      (node (ref "P1") (pin "14") (pinfunction "GND_14") (pintype "passive"))
      (node (ref "P1") (pin "8") (pinfunction "GND_8") (pintype "passive"))
      (node (ref "P10") (pin "5") (pinfunction "GND_5") (pintype "passive"))
      (node (ref "P11") (pin "15") (pinfunction "15_15") (pintype "passive"))
      (node (ref "P11") (pin "7") (pinfunction "7_7") (pintype "passive"))
      (node (ref "P11") (pin "8") (pinfunction "8_8") (pintype "passive"))
      (node (ref "P2") (pin "2") (pinfunction "2_2") (pintype "passive"))
      (node (ref "P3") (pin "3") (pinfunction "3_3") (pintype "passive"))
      (node (ref "P4") (pin "15") (pinfunction "15_15") (pintype "passive"))
      (node (ref "P4") (pin "24") (pinfunction "24_24") (pintype "passive"))
      (node (ref "P4") (pin "33") (pinfunction "33_33") (pintype "passive"))
      (node (ref "P4") (pin "44") (pinfunction "44_44") (pintype "passive"))
      (node (ref "P4") (pin "50") (pinfunction "50_50") (pintype "passive"))
      (node (ref "P4") (pin "51") (pinfunction "51_51") (pintype "passive"))
      (node (ref "P4") (pin "6") (pinfunction "6_6") (pintype "passive"))
      (node (ref "P5") (pin "4") (pinfunction "4_4") (pintype "passive"))
      (node (ref "P5") (pin "5") (pinfunction "5_5") (pintype "passive"))
      (node (ref "P5") (pin "6") (pinfunction "6_6") (pintype "passive"))
      (node (ref "P6") (pin "1") (pinfunction "1_1") (pintype "passive"))
      (node (ref "P7") (pin "1") (pinfunction "1_1") (pintype "passive"))
      (node (ref "P8") (pin "1") (pinfunction "1_1") (pintype "passive"))
      (node (ref "Q1") (pin "1") (pinfunction "E_1") (pintype "passive"))
      (node (ref "Q2") (pin "1") (pinfunction "E_1") (pintype "passive"))
      (node (ref "R12") (pin "2") (pinfunction "2_2") (pintype "passive"))
      (node (ref "R14") (pin "2") (pinfunction "2_2") (pintype "passive"))
      (node (ref "R15") (pin "1") (pinfunction "1_1") (pintype "passive"))
      (node (ref "R16") (pin "1") (pinfunction "1_1") (pintype "passive"))
      (node (ref "R17") (pin "1") (pinfunction "1_1") (pintype "passive"))
      (node (ref "R27") (pin "1") (pinfunction "1_1") (pintype "passive"))
      (node (ref "R8") (pin "1") (pinfunction "1_1") (pintype "passive"))
      (node (ref "R9") (pin "1") (pinfunction "1_1") (pintype "passive"))
      (node (ref "U1") (pin "1") (pintype "passive"))
      (node (ref "U1") (pin "128") (pintype "passive"))
      (node (ref "U1") (pin "149") (pintype "passive"))
      (node (ref "U1") (pin "176") (pintype "passive"))
      (node (ref "U1") (pin "201") (pintype "passive"))
      (node (ref "U1") (pin "202") (pintype "passive"))
      (node (ref "U1") (pin "3") (pintype "passive"))
      (node (ref "U1") (pin "5") (pintype "passive"))
      (node (ref "U1") (pin "51") (pintype "passive"))
      (node (ref "U1") (pin "65") (pintype "passive"))
      (node (ref "U1") (pin "7") (pintype "passive"))
      (node (ref "U1") (pin "9") (pintype "passive"))
      (node (ref "U1") (pin "93") (pintype "passive"))
      (node (ref "U2") (pin "25") (pinfunction "VSS_25") (pintype "passive"))
      (node (ref "U3") (pin "6") (pinfunction "GND_6") (pintype "passive"))
      (node (ref "U3") (pin "9") (pinfunction "GND_9") (pintype "passive"))
      (node (ref "U4") (pin "3") (pinfunction "GND_3") (pintype "passive"))
      (node (ref "U4") (pin "6") (pinfunction "GND_6") (pintype "passive"))
      (node (ref "U5") (pin "21") (pinfunction "GND_21") (pintype "power_in"))
      (node (ref "U5") (pin "3") (pinfunction "GND_3") (pintype "power_in"))
      (node (ref "U5") (pin "5") (pinfunction "GND_5") (pintype "power_in"))
      (node (ref "U6") (pin "11") (pinfunction "GND_11") (pintype "passive"))
      (node (ref "U7") (pin "2") (pinfunction "VSS_2") (pintype "passive"))
      (node (ref "U8") (pin "1") (pinfunction "AGND_1") (pintype "passive"))
      (node (ref "U8") (pin "31") (pinfunction "SIM_GND_31") (pintype "passive"))
      (node (ref "U8") (pin "35") (pinfunction "GND_35") (pintype "passive"))
      (node (ref "U8") (pin "36") (pinfunction "GND_36") (pintype "passive"))
      (node (ref "U8") (pin "37") (pinfunction "GND_37") (pintype "passive"))
      (node (ref "U8") (pin "38") (pinfunction "GND_38") (pintype "passive"))
      (node (ref "U8") (pin "40") (pinfunction "GND_40") (pintype "passive"))
    )
    (net (code "230") (name "Net-(C26-Pad2)") (class "Default")
      (node (ref "C26") (pin "2") (pintype "passive"))
      (node (ref "P11") (pin "6") (pinfunction "6_6") (pintype "passive"))
    )
    (net (code "231") (name "Net-(D2-K)") (class "Default")
      (node (ref "C20") (pin "1") (pinfunction "1_1") (pintype "passive"))
      (node (ref "D2") (pin "2") (pinfunction "K_2") (pintype "passive"))
      (node (ref "L2") (pin "1") (pinfunction "1_1") (pintype "passive"))
      (node (ref "U3") (pin "8") (pinfunction "SW_8") (pintype "passive"))
    )
    (net (code "232") (name "Net-(D3-K)") (class "Default")
      (node (ref "D3") (pin "2") (pinfunction "K_2") (pintype "passive"))
      (node (ref "R15") (pin "2") (pinfunction "2_2") (pintype "passive"))
    )
    (net (code "233") (name "Net-(D4-K)") (class "Default")
      (node (ref "D4") (pin "2") (pinfunction "K_2") (pintype "passive"))
      (node (ref "R16") (pin "2") (pinfunction "2_2") (pintype "passive"))
    )
    (net (code "234") (name "Net-(D5-K)") (class "Default")
      (node (ref "D5") (pin "2") (pinfunction "K_2") (pintype "passive"))
      (node (ref "R23") (pin "2") (pinfunction "2_2") (pintype "passive"))
    )
    (net (code "235") (name "Net-(P1-LED_G-)") (class "Default")
      (node (ref "P1") (pin "10") (pinfunction "LED_G-_10") (pintype "passive"))
      (node (ref "R7") (pin "1") (pinfunction "1_1") (pintype "passive"))
    )
    (net (code "236") (name "Net-(P1-LED_Y+)") (class "Default")
      (node (ref "P1") (pin "12") (pinfunction "LED_Y+_12") (pintype "passive"))
      (node (ref "R6") (pin "1") (pinfunction "1_1") (pintype "passive"))
    )
    (net (code "237") (name "Net-(P1-MRD)") (class "Default")
      (node (ref "C1") (pin "1") (pintype "passive"))
      (node (ref "P1") (pin "4") (pinfunction "MTD_4") (pintype "passive"))
      (node (ref "P1") (pin "5") (pinfunction "MRD_5") (pintype "passive"))
      (node (ref "R1") (pin "1") (pinfunction "1_1") (pintype "passive"))
    )
    (net (code "238") (name "Net-(P4-Pad37)") (class "Default")
      (node (ref "P4") (pin "37") (pinfunction "37_37") (pintype "passive"))
      (node (ref "R18") (pin "2") (pinfunction "2_2") (pintype "passive"))
    )
    (net (code "239") (name "Net-(Q1-B)") (class "Default")
      (node (ref "Q1") (pin "2") (pinfunction "B_2") (pintype "passive"))
      (node (ref "R33") (pin "1") (pinfunction "1_1") (pintype "passive"))
    )
    (net (code "240") (name "Net-(Q1-C)") (class "Default")
      (node (ref "Q1") (pin "3") (pinfunction "C_3") (pintype "passive"))
      (node (ref "U8") (pin "10") (pinfunction "PWRKEY_10") (pintype "passive"))
    )
    (net (code "241") (name "Net-(Q2-B)") (class "Default")
      (node (ref "Q2") (pin "2") (pinfunction "B_2") (pintype "passive"))
      (node (ref "R34") (pin "1") (pinfunction "1_1") (pintype "passive"))
    )
    (net (code "242") (name "Net-(Q2-C)") (class "Default")
      (node (ref "C17") (pin "1") (pinfunction "1_1") (pintype "passive"))
      (node (ref "Q2") (pin "3") (pinfunction "C_3") (pintype "passive"))
      (node (ref "U8") (pin "11") (pinfunction "RESET_11") (pintype "passive"))
    )
    (net (code "243") (name "Net-(R13-Pad1)") (class "Default")
      (node (ref "R13") (pin "1") (pinfunction "1_1") (pintype "passive"))
      (node (ref "R14") (pin "1") (pinfunction "1_1") (pintype "passive"))
      (node (ref "U3") (pin "4") (pinfunction "SW_4") (pintype "passive"))
    )
    (net (code "244") (name "Net-(U2-RBIAS)") (class "Default")
      (node (ref "R9") (pin "2") (pinfunction "2_2") (pintype "passive"))
      (node (ref "U2") (pin "24") (pinfunction "RBIAS_24") (pintype "passive"))
    )
    (net (code "245") (name "Net-(U2-VDDCR)") (class "Default")
      (node (ref "C5") (pin "1") (pintype "passive"))
      (node (ref "C6") (pin "1") (pintype "passive"))
      (node (ref "U2") (pin "6") (pinfunction "VDDCR_6") (pintype "passive"))
    )
    (net (code "246") (name "Net-(U2-XTAL1{slash}CLKIN)") (class "Default")
      (node (ref "R19") (pin "1") (pinfunction "1_1") (pintype "passive"))
      (node (ref "U2") (pin "5") (pinfunction "XTAL1/CLKIN_5") (pintype "passive"))
    )
    (net (code "247") (name "Net-(U3-BOOT)") (class "Default")
      (node (ref "C20") (pin "2") (pinfunction "2_2") (pintype "passive"))
      (node (ref "U3") (pin "1") (pinfunction "BOOT_1") (pintype "passive"))
    )
    (net (code "248") (name "Net-(U4-NR{slash}FB)") (class "Default")
      (node (ref "R11") (pin "1") (pinfunction "1_1") (pintype "passive"))
      (node (ref "R12") (pin "1") (pinfunction "1_1") (pintype "passive"))
      (node (ref "U4") (pin "4") (pinfunction "NR/FB_4") (pintype "passive"))
    )
    (net (code "249") (name "Net-(U5-AREF)") (class "Default")
      (node (ref "C23") (pin "1") (pinfunction "1_1") (pintype "passive"))
      (node (ref "U5") (pin "20") (pinfunction "AREF_20") (pintype "passive"))
    )
    (net (code "250") (name "Net-(U5-PC0_(ADC0))") (class "Default")
      (node (ref "R36") (pin "2") (pinfunction "2_2") (pintype "passive"))
      (node (ref "U5") (pin "23") (pinfunction "PC0_(ADC0)_23") (pintype "bidirectional"))
    )
    (net (code "251") (name "Net-(U5-PD4_(XCK{slash}T0))") (class "Default")
      (node (ref "R23") (pin "1") (pinfunction "1_1") (pintype "passive"))
      (node (ref "U5") (pin "2") (pinfunction "PD4_(XCK/T0)_2") (pintype "bidirectional"))
    )
    (net (code "252") (name "Net-(U8-DTR)") (class "Default")
      (node (ref "R35") (pin "1") (pinfunction "1_1") (pintype "passive"))
      (node (ref "U8") (pin "20") (pinfunction "DTR_20") (pintype "passive"))
    )
    (net (code "253") (name "Net-(U8-NETLIGHT)") (class "Default")
      (node (ref "R25") (pin "1") (pinfunction "1_1") (pintype "passive"))
      (node (ref "U8") (pin "13") (pinfunction "NETLIGHT_13") (pintype "passive"))
    )
    (net (code "254") (name "Net-(U8-RF_ANT)") (class "Default")
      (node (ref "A1") (pin "1") (pinfunction "1_1") (pintype "passive"))
      (node (ref "U8") (pin "39") (pinfunction "RF_ANT_39") (pintype "passive"))
    )
    (net (code "255") (name "Net-(U8-RX)") (class "Default")
      (node (ref "R31") (pin "1") (pinfunction "1_1") (pintype "passive"))
      (node (ref "U8") (pin "22") (pinfunction "RX_22") (pintype "passive"))
    )
    (net (code "256") (name "Net-(U8-SIM_CLK)") (class "Default")
      (node (ref "R26") (pin "2") (pinfunction "2_2") (pintype "passive"))
      (node (ref "U8") (pin "30") (pinfunction "SIM_CLK_30") (pintype "passive"))
    )
    (net (code "257") (name "Net-(U8-SIM_DATA)") (class "Default")
      (node (ref "R29") (pin "2") (pinfunction "2_2") (pintype "passive"))
      (node (ref "U8") (pin "29") (pinfunction "SIM_DATA_29") (pintype "passive"))
    )
    (net (code "258") (name "Net-(U8-SIM_RST)") (class "Default")
      (node (ref "R30") (pin "2") (pinfunction "2_2") (pintype "passive"))
      (node (ref "U8") (pin "28") (pinfunction "SIM_RST_28") (pintype "passive"))
    )
    (net (code "259") (name "Net-(U8-TX)") (class "Default")
      (node (ref "R32") (pin "1") (pinfunction "1_1") (pintype "passive"))
      (node (ref "U8") (pin "21") (pinfunction "TX_21") (pintype "passive"))
    )
    (net (code "260") (name "VDD3.0") (class "Default")
      (node (ref "R35") (pin "2") (pinfunction "2_2") (pintype "passive"))
      (node (ref "U8") (pin "19") (pinfunction "VDD_EXT_19") (pintype "passive"))
    )
    (net (code "261") (name "VSIM") (class "Default")
      (node (ref "P10") (pin "1") (pinfunction "VCC_1") (pintype "passive"))
      (node (ref "U8") (pin "27") (pinfunction "SIM_VDD_27") (pintype "passive"))
    )
    (net (code "262") (name "unconnected-(P1-NC-Pad7)") (class "Default")
      (node (ref "P1") (pin "7") (pinfunction "NC_7") (pintype "passive+no_connect"))
    )
    (net (code "263") (name "unconnected-(P4-Pad34)") (class "Default")
      (node (ref "P4") (pin "34") (pinfunction "34_34") (pintype "passive"))
    )
    (net (code "264") (name "unconnected-(P4-Pad35)") (class "Default")
      (node (ref "P4") (pin "35") (pinfunction "35_35") (pintype "passive"))
    )
    (net (code "265") (name "unconnected-(P4-Pad36)") (class "Default")
      (node (ref "P4") (pin "36") (pinfunction "36_36") (pintype "passive"))
    )
    (net (code "266") (name "unconnected-(P4-Pad38)") (class "Default")
      (node (ref "P4") (pin "38") (pinfunction "38_38") (pintype "passive"))
    )
    (net (code "267") (name "unconnected-(P4-Pad39)") (class "Default")
      (node (ref "P4") (pin "39") (pinfunction "39_39") (pintype "passive"))
    )
    (net (code "268") (name "unconnected-(P4-Pad40)") (class "Default")
      (node (ref "P4") (pin "40") (pinfunction "40_40") (pintype "passive"))
    )
    (net (code "269") (name "unconnected-(P4-Pad41)") (class "Default")
      (node (ref "P4") (pin "41") (pinfunction "41_41") (pintype "passive"))
    )
    (net (code "270") (name "unconnected-(P4-Pad45)") (class "Default")
      (node (ref "P4") (pin "45") (pinfunction "45_45") (pintype "passive"))
    )
    (net (code "271") (name "unconnected-(P4-Pad46)") (class "Default")
      (node (ref "P4") (pin "46") (pinfunction "46_46") (pintype "passive"))
    )
    (net (code "272") (name "unconnected-(P4-Pad47)") (class "Default")
      (node (ref "P4") (pin "47") (pinfunction "47_47") (pintype "passive"))
    )
    (net (code "273") (name "unconnected-(P4-Pad49)") (class "Default")
      (node (ref "P4") (pin "49") (pinfunction "49_49") (pintype "passive"))
    )
    (net (code "274") (name "unconnected-(P10-NC-Pad4)") (class "Default")
      (node (ref "P10") (pin "4") (pinfunction "NC_4") (pintype "passive"))
    )
    (net (code "275") (name "unconnected-(P10-NC-Pad8)") (class "Default")
      (node (ref "P10") (pin "8") (pinfunction "NC_8") (pintype "passive"))
    )
    (net (code "276") (name "unconnected-(P10-VPP-Pad6)") (class "Default")
      (node (ref "P10") (pin "6") (pinfunction "VPP_6") (pintype "passive"))
    )
    (net (code "277") (name "unconnected-(U1-Pad108)") (class "Default")
      (node (ref "U1") (pin "108") (pintype "passive"))
    )
    (net (code "278") (name "unconnected-(U2-XTAL2-Pad4)") (class "Default")
      (node (ref "U2") (pin "4") (pinfunction "XTAL2_4") (pintype "passive+no_connect"))
    )
    (net (code "279") (name "unconnected-(U3-EN-Pad5)") (class "Default")
      (node (ref "U3") (pin "5") (pinfunction "EN_5") (pintype "passive"))
    )
    (net (code "280") (name "unconnected-(U5-ADC6-Pad19)") (class "Default")
      (node (ref "U5") (pin "19") (pinfunction "ADC6_19") (pintype "input"))
    )
    (net (code "281") (name "unconnected-(U5-ADC7-Pad22)") (class "Default")
      (node (ref "U5") (pin "22") (pinfunction "ADC7_22") (pintype "input"))
    )
    (net (code "282") (name "unconnected-(U5-PB1_(OC1A)-Pad13)") (class "Default")
      (node (ref "U5") (pin "13") (pinfunction "PB1_(OC1A)_13") (pintype "bidirectional"))
    )
    (net (code "283") (name "unconnected-(U5-PB2_(~{SS}{slash}OC1B)-Pad14)") (class "Default")
      (node (ref "U5") (pin "14") (pinfunction "PB2_(~{SS}/OC1B)_14") (pintype "bidirectional"))
    )
    (net (code "284") (name "unconnected-(U5-PB6_(XTAL1{slash}TOSC1)-Pad7)") (class "Default")
      (node (ref "U5") (pin "7") (pinfunction "PB6_(XTAL1/TOSC1)_7") (pintype "bidirectional"))
    )
    (net (code "285") (name "unconnected-(U5-PB7_(XTAL2{slash}TOSC2)-Pad8)") (class "Default")
      (node (ref "U5") (pin "8") (pinfunction "PB7_(XTAL2/TOSC2)_8") (pintype "bidirectional"))
    )
    (net (code "286") (name "unconnected-(U5-PC1_(ADC1)-Pad24)") (class "Default")
      (node (ref "U5") (pin "24") (pinfunction "PC1_(ADC1)_24") (pintype "bidirectional"))
    )
    (net (code "287") (name "unconnected-(U5-PC2_(ADC2)-Pad25)") (class "Default")
      (node (ref "U5") (pin "25") (pinfunction "PC2_(ADC2)_25") (pintype "bidirectional"))
    )
    (net (code "288") (name "unconnected-(U5-PC3_(ADC3)-Pad26)") (class "Default")
      (node (ref "U5") (pin "26") (pinfunction "PC3_(ADC3)_26") (pintype "bidirectional"))
    )
    (net (code "289") (name "unconnected-(U5-PC4_(ADC4{slash}SDA)-Pad27)") (class "Default")
      (node (ref "U5") (pin "27") (pinfunction "PC4_(ADC4/SDA)_27") (pintype "bidirectional"))
    )
    (net (code "290") (name "unconnected-(U5-PC5_(ADC5{slash}SCL)-Pad28)") (class "Default")
      (node (ref "U5") (pin "28") (pinfunction "PC5_(ADC5/SCL)_28") (pintype "bidirectional"))
    )
    (net (code "291") (name "unconnected-(U5-PD2_(INT0)-Pad32)") (class "Default")
      (node (ref "U5") (pin "32") (pinfunction "PD2_(INT0)_32") (pintype "bidirectional"))
    )
    (net (code "292") (name "unconnected-(U5-PD3_(INT1)-Pad1)") (class "Default")
      (node (ref "U5") (pin "1") (pinfunction "PD3_(INT1)_1") (pintype "bidirectional"))
    )
    (net (code "293") (name "unconnected-(U5-PD5_(T1)-Pad9)") (class "Default")
      (node (ref "U5") (pin "9") (pinfunction "PD5_(T1)_9") (pintype "bidirectional"))
    )
    (net (code "294") (name "unconnected-(U5-PD6_(AIN0)-Pad10)") (class "Default")
      (node (ref "U5") (pin "10") (pinfunction "PD6_(AIN0)_10") (pintype "bidirectional"))
    )
    (net (code "295") (name "unconnected-(U6-A8-Pad9)") (class "Default")
      (node (ref "U6") (pin "9") (pinfunction "A8_9") (pintype "passive"))
    )
    (net (code "296") (name "unconnected-(U6-B8-Pad12)") (class "Default")
      (node (ref "U6") (pin "12") (pinfunction "B8_12") (pintype "passive"))
    )
    (net (code "297") (name "unconnected-(U7-NC-Pad4)") (class "Default")
      (node (ref "U7") (pin "4") (pinfunction "NC_4") (pintype "passive"))
    )
    (net (code "298") (name "unconnected-(U8-ADC-Pad16)") (class "Default")
      (node (ref "U8") (pin "16") (pinfunction "ADC_16") (pintype "passive"))
    )
    (net (code "299") (name "unconnected-(U8-CTS-Pad23)") (class "Default")
      (node (ref "U8") (pin "23") (pinfunction "CTS_23") (pintype "passive"))
    )
    (net (code "300") (name "unconnected-(U8-DBG_R-Pad14)") (class "Default")
      (node (ref "U8") (pin "14") (pinfunction "DBG_R_14") (pintype "passive"))
    )
    (net (code "301") (name "unconnected-(U8-DBG_T-Pad15)") (class "Default")
      (node (ref "U8") (pin "15") (pinfunction "DBG_T_15") (pintype "passive"))
    )
    (net (code "302") (name "unconnected-(U8-DCD-Pad25)") (class "Default")
      (node (ref "U8") (pin "25") (pinfunction "DCD_25") (pintype "passive"))
    )
    (net (code "303") (name "unconnected-(U8-GPIO-Pad17)") (class "Default")
      (node (ref "U8") (pin "17") (pinfunction "GPIO_17") (pintype "passive"))
    )
    (net (code "304") (name "unconnected-(U8-GPIO-Pad18)") (class "Default")
      (node (ref "U8") (pin "18") (pinfunction "GPIO_18") (pintype "passive"))
    )
    (net (code "305") (name "unconnected-(U8-LOUDSPKN-Pad8)") (class "Default")
      (node (ref "U8") (pin "8") (pinfunction "LOUDSPKN_8") (pintype "passive"))
    )
    (net (code "306") (name "unconnected-(U8-LOUDSPKP-Pad9)") (class "Default")
      (node (ref "U8") (pin "9") (pinfunction "LOUDSPKP_9") (pintype "passive"))
    )
    (net (code "307") (name "unconnected-(U8-MIC1N-Pad5)") (class "Default")
      (node (ref "U8") (pin "5") (pinfunction "MIC1N_5") (pintype "passive"))
    )
    (net (code "308") (name "unconnected-(U8-MIC1P-Pad4)") (class "Default")
      (node (ref "U8") (pin "4") (pinfunction "MIC1P_4") (pintype "passive"))
    )
    (net (code "309") (name "unconnected-(U8-MIC2N-Pad3)") (class "Default")
      (node (ref "U8") (pin "3") (pinfunction "MIC2N_3") (pintype "passive"))
    )
    (net (code "310") (name "unconnected-(U8-MIC2P-Pad2)") (class "Default")
      (node (ref "U8") (pin "2") (pinfunction "MIC2P_2") (pintype "passive"))
    )
    (net (code "311") (name "unconnected-(U8-RI-Pad26)") (class "Default")
      (node (ref "U8") (pin "26") (pinfunction "RI_26") (pintype "passive"))
    )
    (net (code "312") (name "unconnected-(U8-RTS-Pad24)") (class "Default")
      (node (ref "U8") (pin "24") (pinfunction "RTS_24") (pintype "passive"))
    )
    (net (code "313") (name "unconnected-(U8-SPK1N-Pad6)") (class "Default")
      (node (ref "U8") (pin "6") (pinfunction "SPK1N_6") (pintype "passive"))
    )
    (net (code "314") (name "unconnected-(U8-SPK1P-Pad7)") (class "Default")
      (node (ref "U8") (pin "7") (pinfunction "SPK1P_7") (pintype "passive"))
    )
    (net (code "315") (name "unconnected-(U8-VRTC-Pad32)") (class "Default")
      (node (ref "U8") (pin "32") (pinfunction "VRTC_32") (pintype "passive"))
    )
  )
)
